# untitled.net
KiCad netlist of a schematic drawn in EAGLE
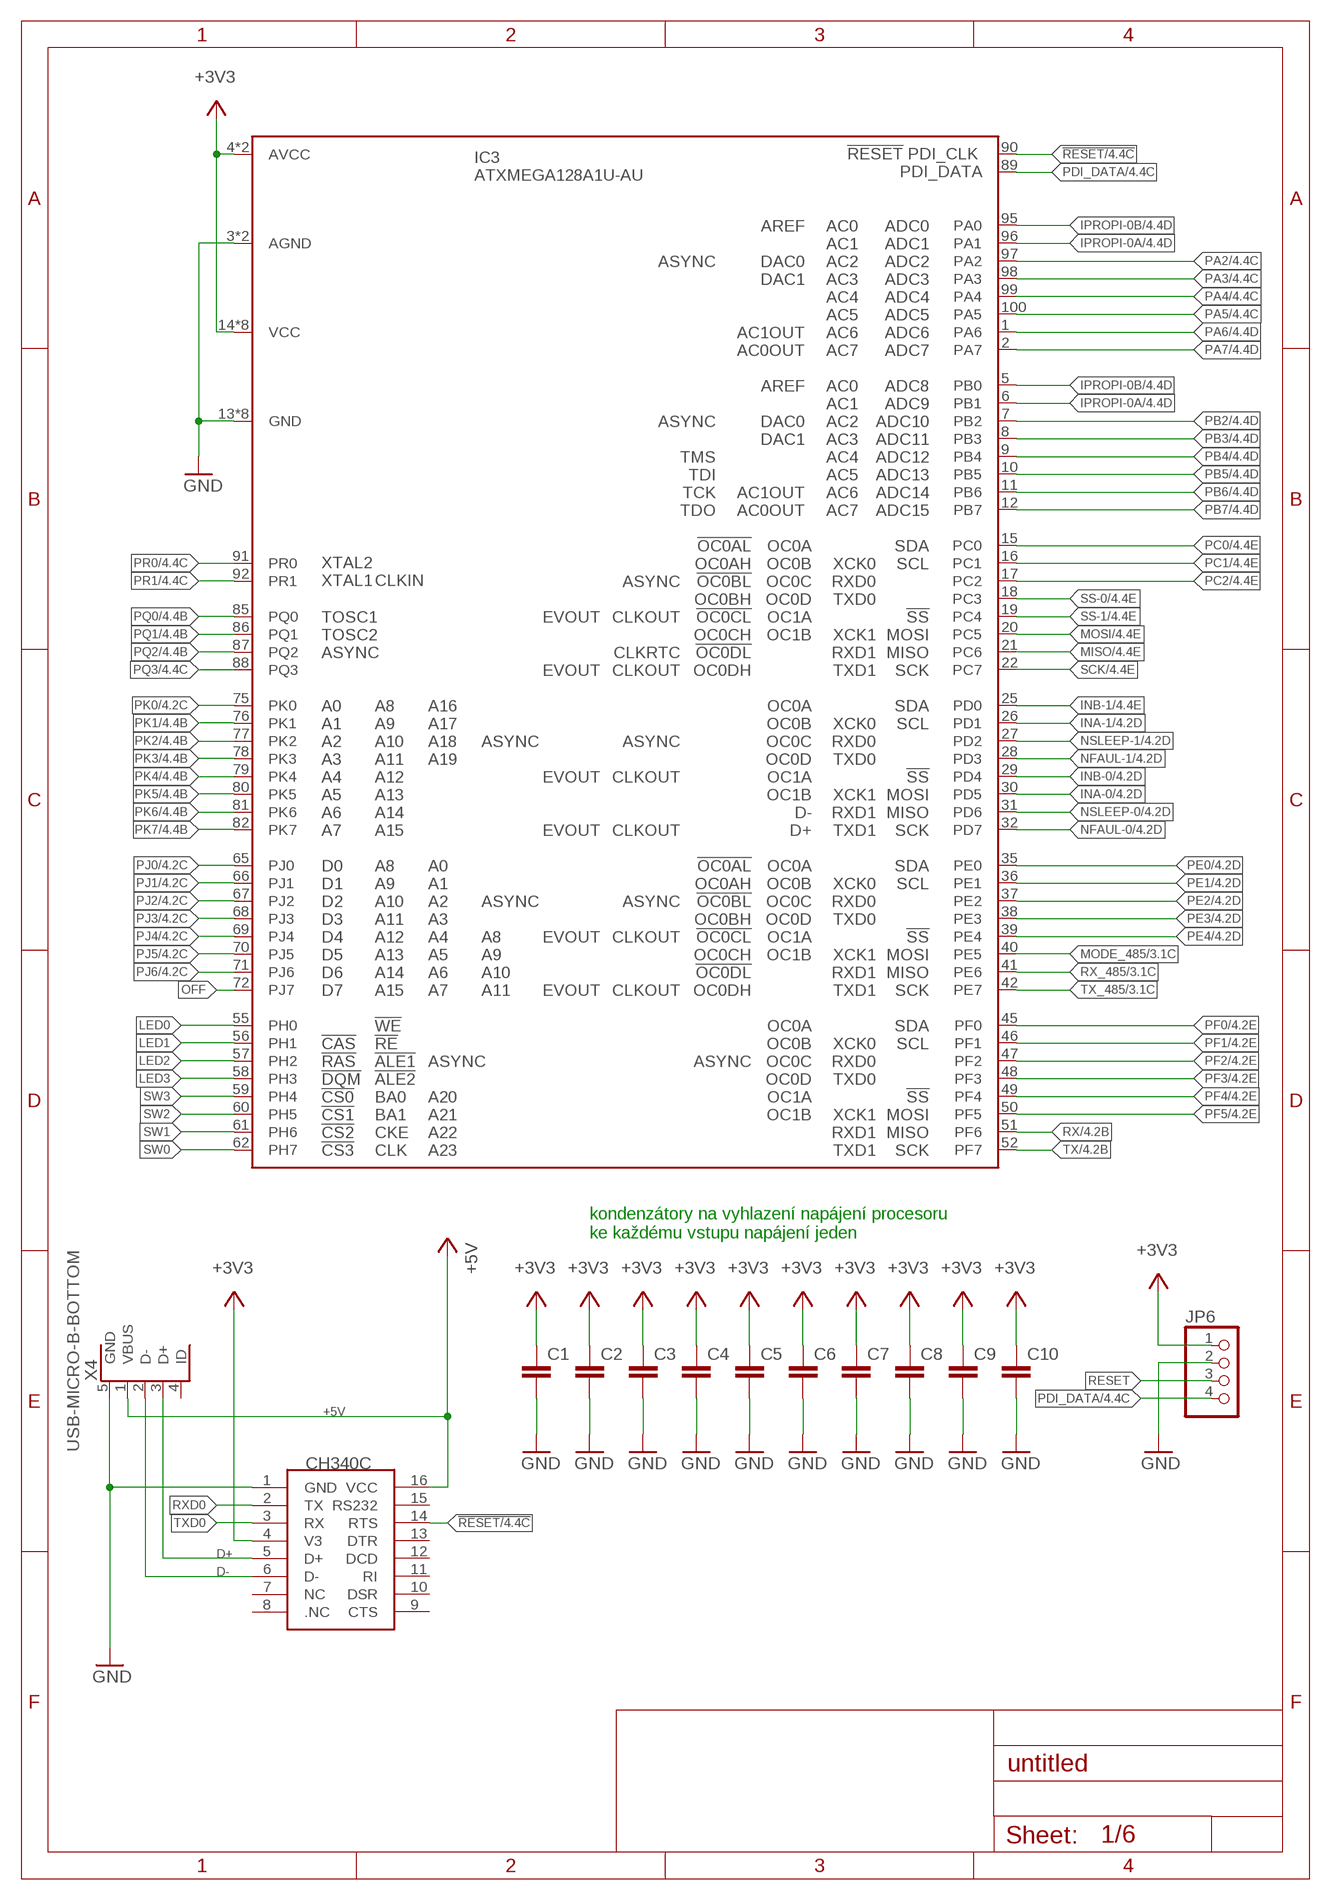
[diagram p0: schematic, sheet 1]
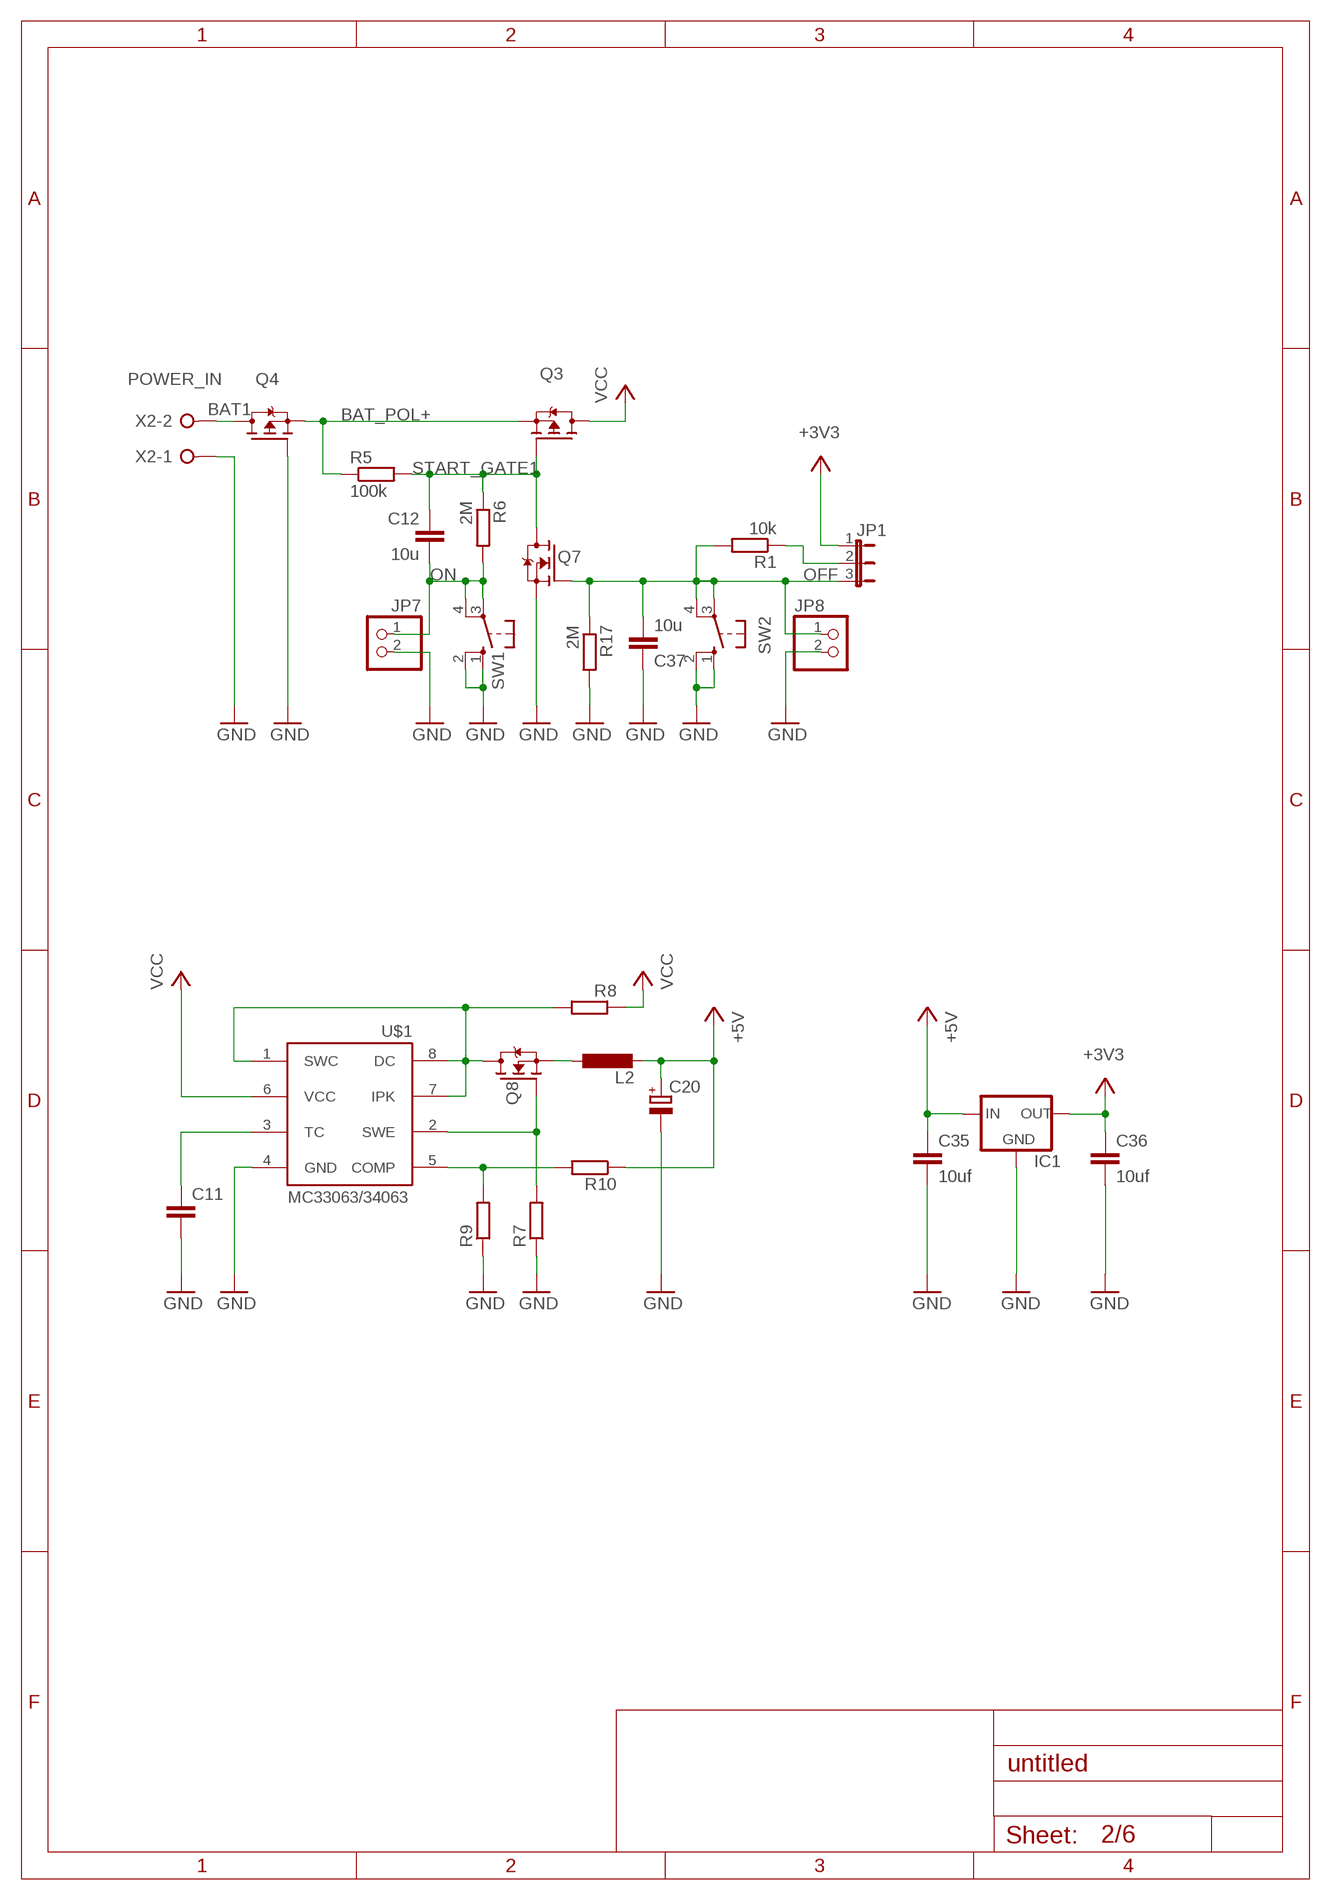
[diagram p1: schematic, sheet 2]
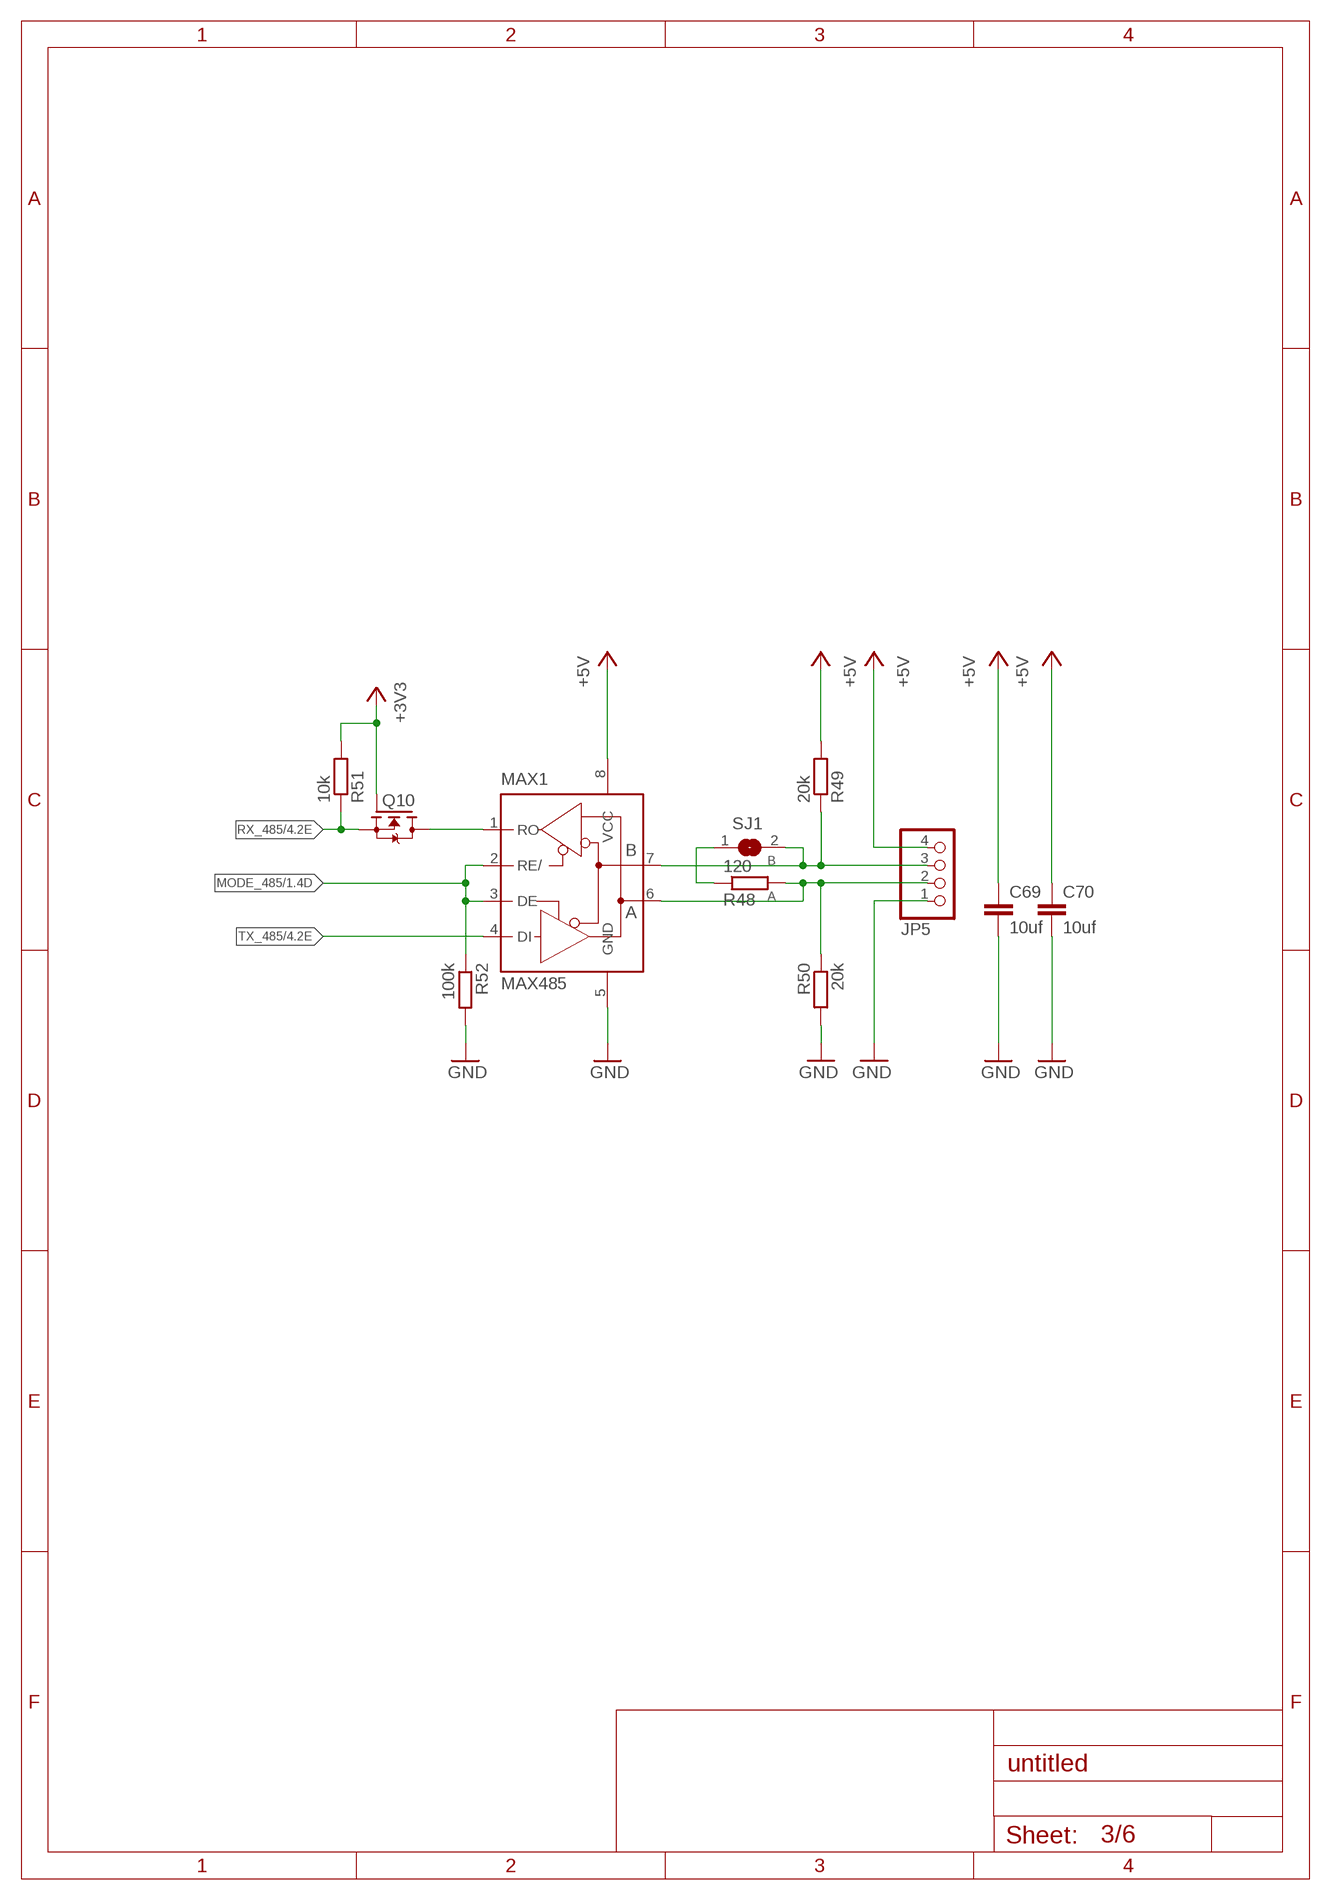
[diagram p2: schematic, sheet 3]
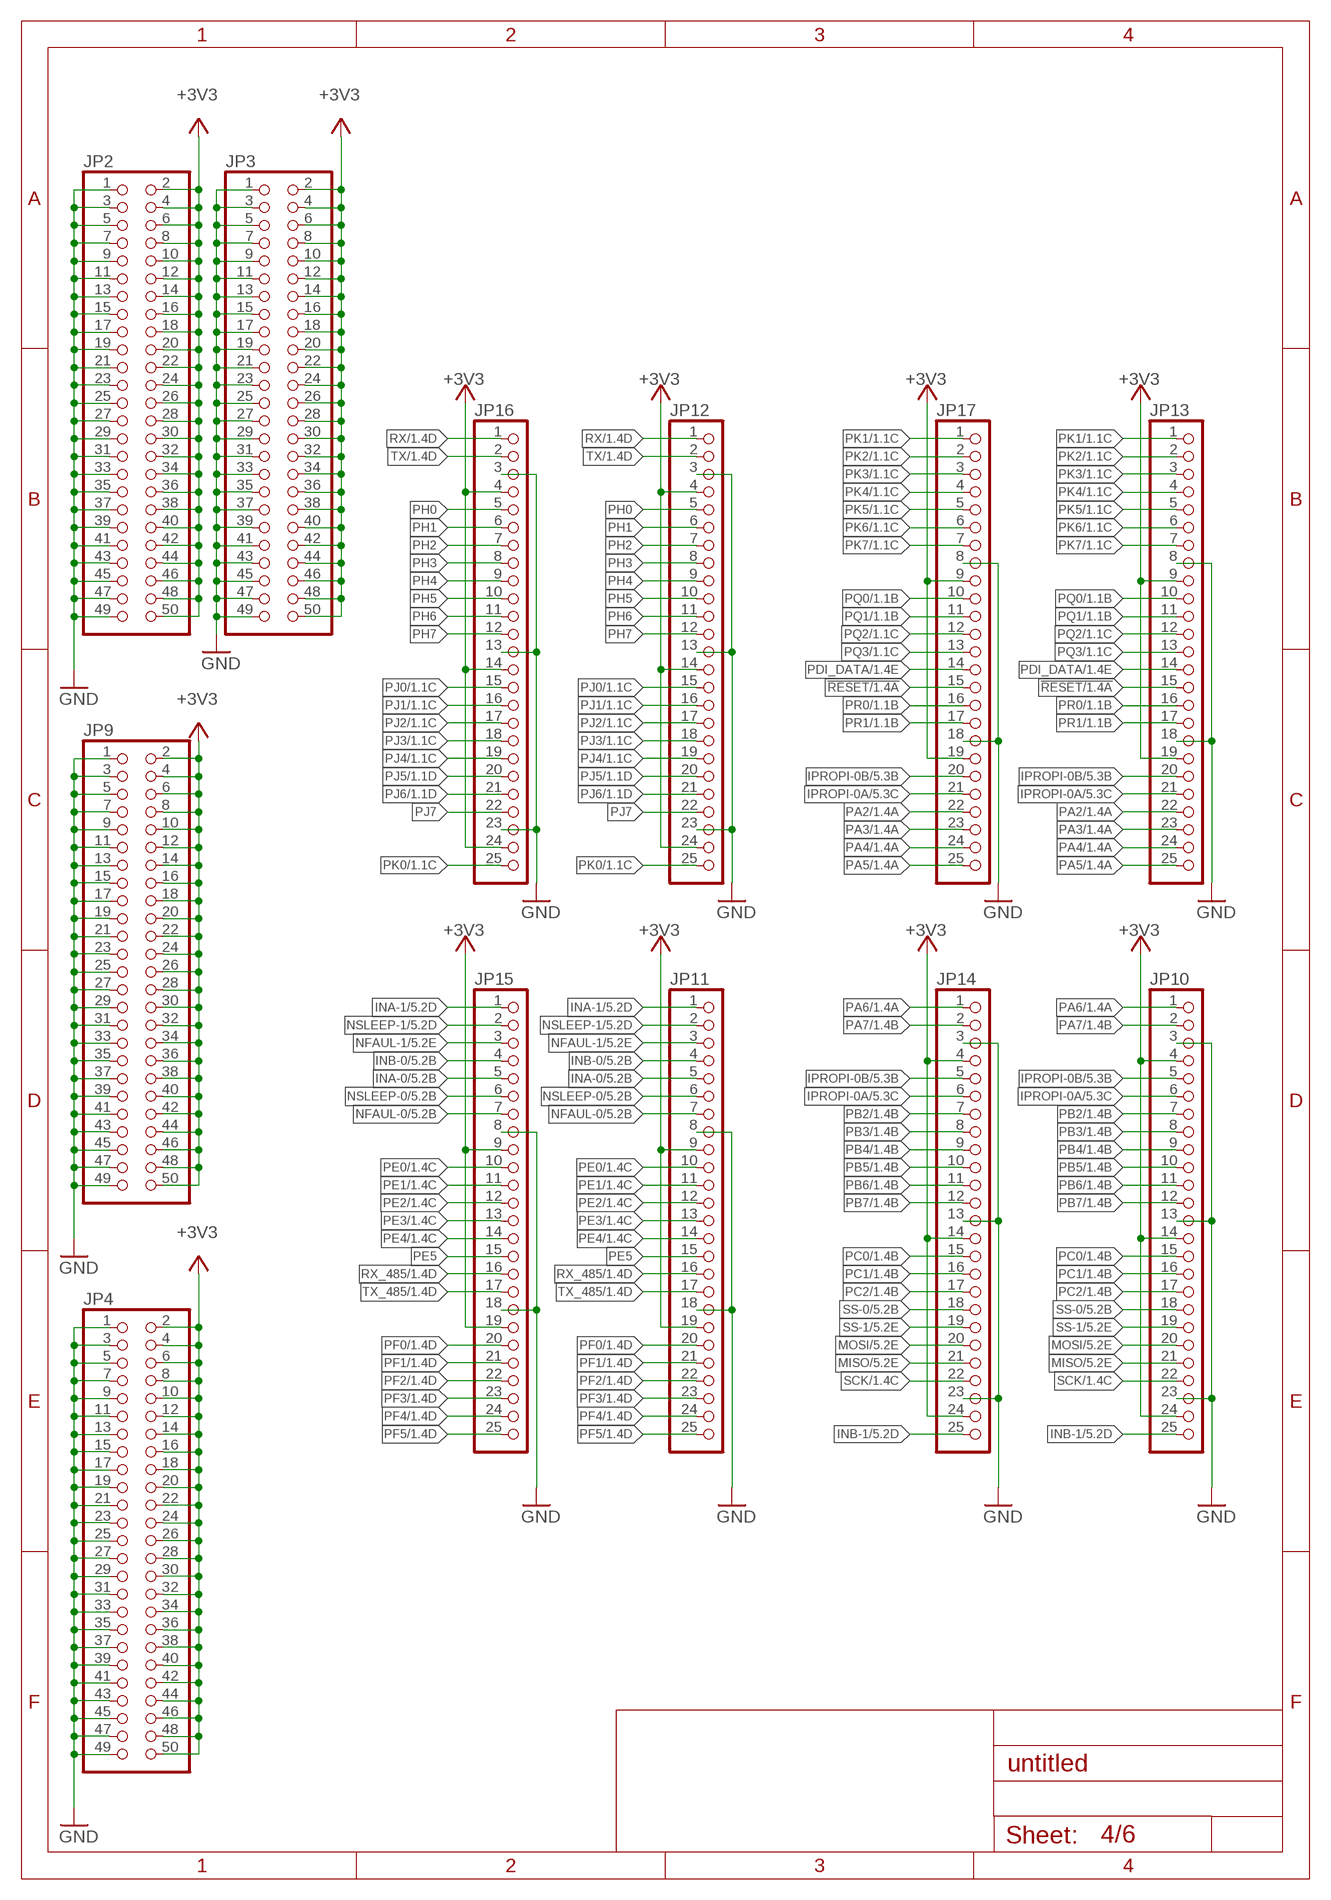
[diagram p3: schematic, sheet 4]
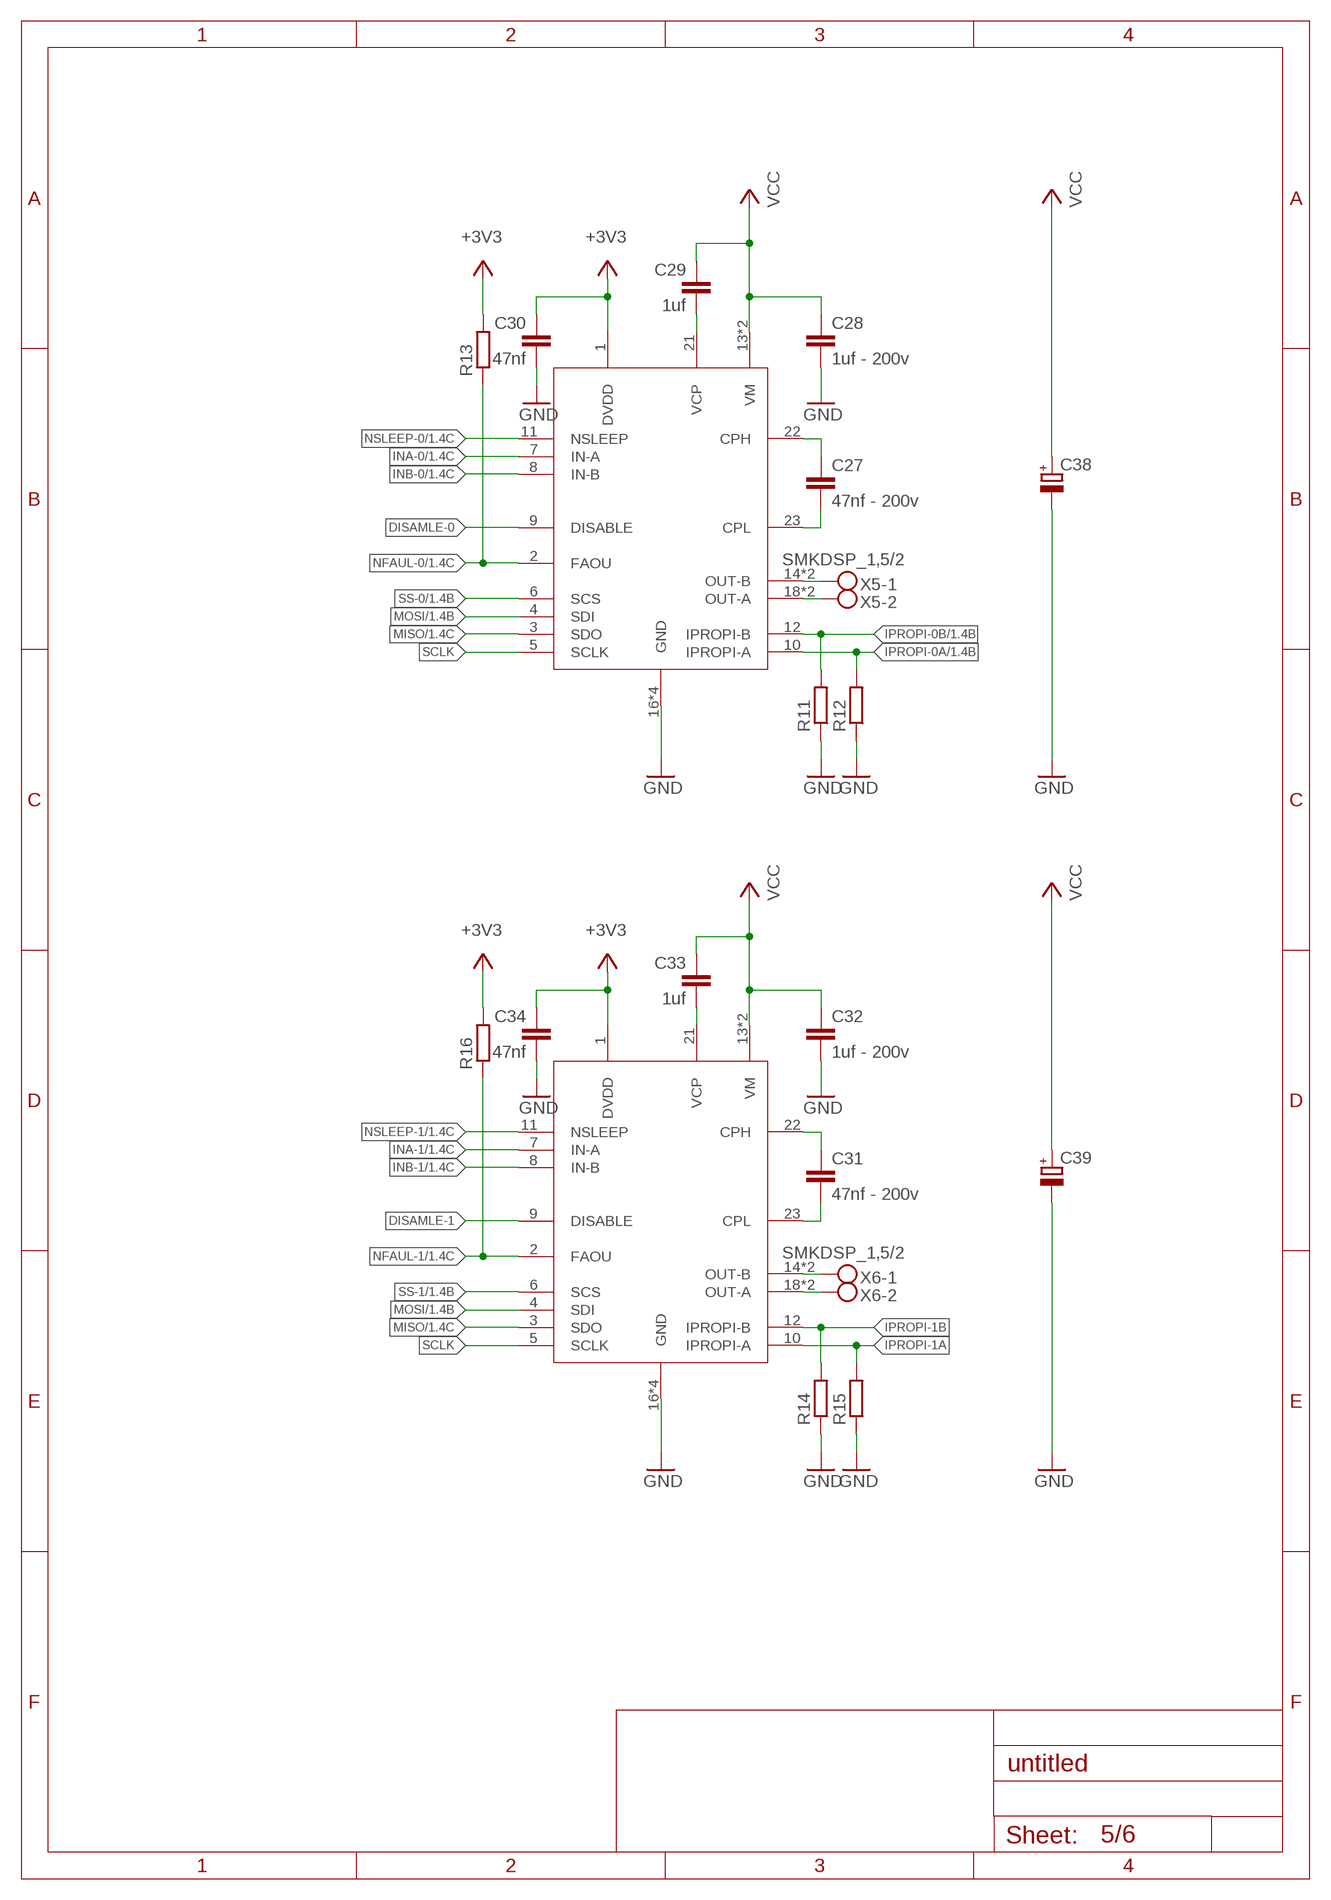
[diagram p4: schematic, sheet 5]
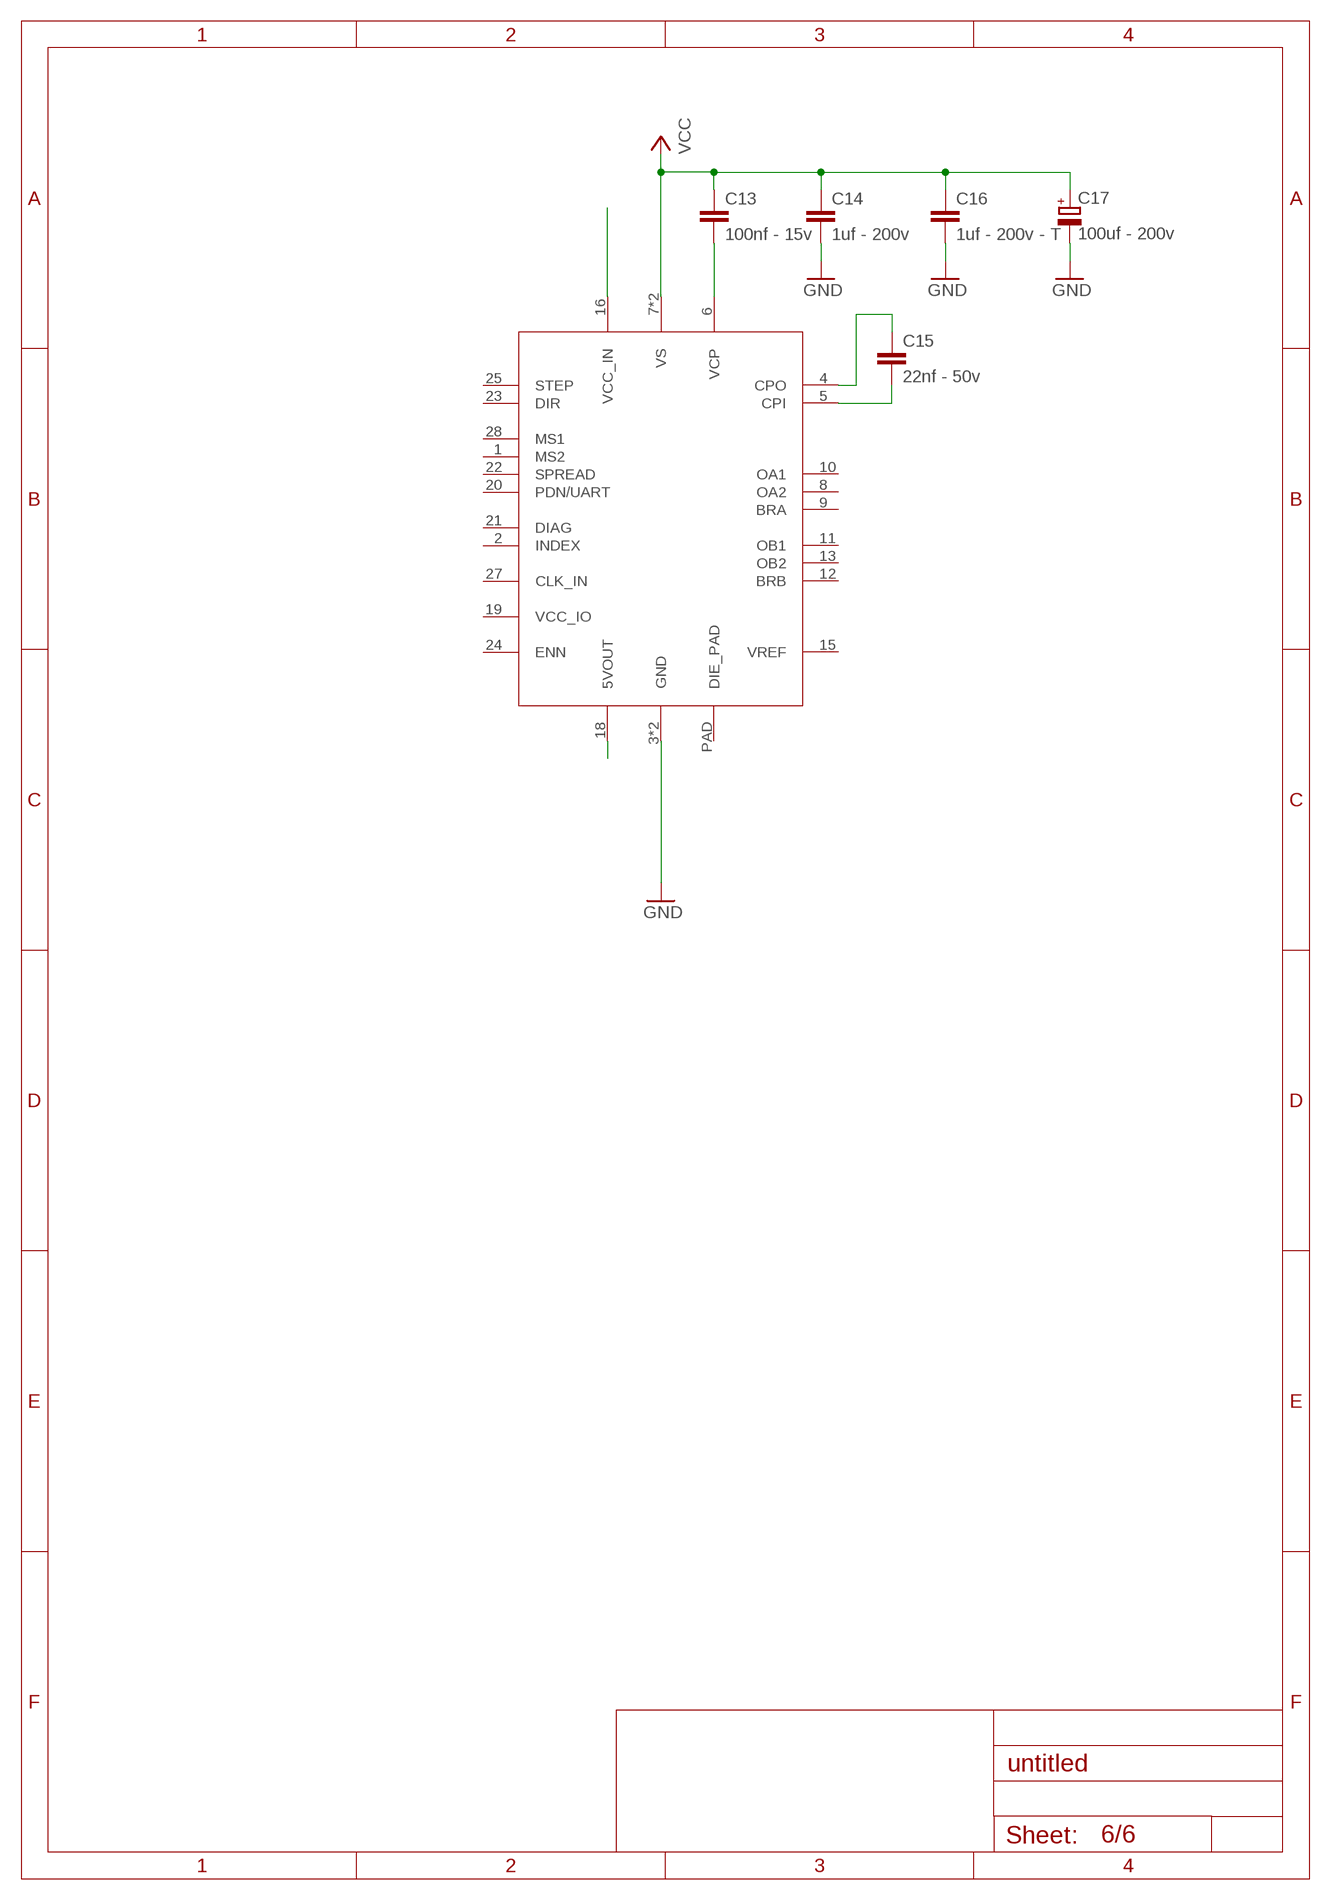
[diagram p5: schematic, sheet 6]

(export (version "E")
  (design (tool "Eeschema 10.0.6"))
  (components
    (comp (ref "C13")
      (value "100nf - 15v")
      (footprint "eagle-import:C1206")
      (libsource (lib "eagle-import") (part "rcl_334_C-EUC1206"))
    )
    (comp (ref "C14")
      (value "1uf - 200v")
      (footprint "eagle-import:C1206")
      (libsource (lib "eagle-import") (part "rcl_334_C-EUC1206"))
    )
    (comp (ref "C15")
      (value "22nf - 50v")
      (footprint "eagle-import:C1206")
      (libsource (lib "eagle-import") (part "rcl_334_C-EUC1206"))
    )
    (comp (ref "C16")
      (value "1uf - 200v - T")
      (footprint "eagle-import:C1206")
      (libsource (lib "eagle-import") (part "rcl_334_C-EUC1206"))
    )
    (comp (ref "C17")
      (value "100uf - 200v")
      (footprint "eagle-import:E5-10,5")
      (libsource (lib "eagle-import") (part "CPOL-EUE5-10.5"))
    )
    (comp (ref "U$3")
      (value "TMC2224")
      (footprint "eagle-import:QFN28")
      (libsource (lib "eagle-import") (part "TMC2224"))
    )
    (comp (ref "JP2")
      (value "PINHD-2X25")
      (footprint "eagle-import:2X25")
      (libsource (lib "eagle-import") (part "PINHD-2X25"))
    )
    (comp (ref "JP3")
      (value "PINHD-2X25")
      (footprint "eagle-import:2X25")
      (libsource (lib "eagle-import") (part "PINHD-2X25"))
    )
    (comp (ref "JP4")
      (value "PINHD-2X25")
      (footprint "eagle-import:2X25")
      (libsource (lib "eagle-import") (part "PINHD-2X25"))
    )
    (comp (ref "JP9")
      (value "PINHD-2X25")
      (footprint "eagle-import:2X25")
      (libsource (lib "eagle-import") (part "PINHD-2X25"))
    )
    (comp (ref "JP10")
      (value "PINHD-1X25")
      (footprint "eagle-import:1X25")
      (libsource (lib "eagle-import") (part "PINHD-1X25"))
    )
    (comp (ref "JP11")
      (value "PINHD-1X25")
      (footprint "eagle-import:1X25")
      (libsource (lib "eagle-import") (part "PINHD-1X25"))
    )
    (comp (ref "JP12")
      (value "PINHD-1X25")
      (footprint "eagle-import:1X25")
      (libsource (lib "eagle-import") (part "PINHD-1X25"))
    )
    (comp (ref "JP13")
      (value "PINHD-1X25")
      (footprint "eagle-import:1X25")
      (libsource (lib "eagle-import") (part "PINHD-1X25"))
    )
    (comp (ref "JP14")
      (value "PINHD-1X25")
      (footprint "eagle-import:1X25")
      (libsource (lib "eagle-import") (part "PINHD-1X25"))
    )
    (comp (ref "JP15")
      (value "PINHD-1X25")
      (footprint "eagle-import:1X25")
      (libsource (lib "eagle-import") (part "PINHD-1X25"))
    )
    (comp (ref "JP16")
      (value "PINHD-1X25")
      (footprint "eagle-import:1X25")
      (libsource (lib "eagle-import") (part "PINHD-1X25"))
    )
    (comp (ref "JP17")
      (value "PINHD-1X25")
      (footprint "eagle-import:1X25")
      (libsource (lib "eagle-import") (part "PINHD-1X25"))
    )
    (comp (ref "C11")
      (value "C-EUC0603")
      (footprint "eagle-import:C0603")
      (libsource (lib "eagle-import") (part "rcl_334_C-EUC0603"))
    )
    (comp (ref "C12")
      (value "10u")
      (footprint "eagle-import:C1206")
      (libsource (lib "eagle-import") (part "rcl_upravena_C-EUC1206"))
    )
    (comp (ref "C20")
      (value "CPOL-EUD")
      (footprint "eagle-import:PANASONIC_D")
      (libsource (lib "eagle-import") (part "rcl_334_CPOL-EUD"))
    )
    (comp (ref "C35")
      (value "10uf")
      (footprint "eagle-import:C0805")
      (libsource (lib "eagle-import") (part "C-EUC0805"))
    )
    (comp (ref "C36")
      (value "10uf")
      (footprint "eagle-import:C0805")
      (libsource (lib "eagle-import") (part "C-EUC0805"))
    )
    (comp (ref "C37")
      (value "10u")
      (footprint "eagle-import:C1206")
      (libsource (lib "eagle-import") (part "rcl_upravena_C-EUC1206"))
    )
    (comp (ref "IC1")
      (value "LM1117")
      (footprint "eagle-import:SOT223")
      (libsource (lib "eagle-import") (part "LM1117"))
    )
    (comp (ref "JP1")
      (value "JP2E")
      (footprint "eagle-import:JP2")
      (libsource (lib "eagle-import") (part "JP2E"))
    )
    (comp (ref "JP7")
      (value "PINHD-1X2")
      (footprint "eagle-import:1X02")
      (libsource (lib "eagle-import") (part "PINHD-1X2"))
    )
    (comp (ref "JP8")
      (value "PINHD-1X2")
      (footprint "eagle-import:1X02")
      (libsource (lib "eagle-import") (part "PINHD-1X2"))
    )
    (comp (ref "L2")
      (value "L-EUL3216C")
      (footprint "eagle-import:L3216C")
      (libsource (lib "eagle-import") (part "L-EUL3216C"))
    )
    (comp (ref "Q3")
      (value "P-MOSFET-MLP_HS")
      (footprint "eagle-import:MLP3.3X3.3_HS")
      (libsource (lib "eagle-import") (part "P-MOSFET-MLP_HS"))
    )
    (comp (ref "Q4")
      (value "P-MOSFET-MLP_HS")
      (footprint "eagle-import:MLP3.3X3.3_HS")
      (libsource (lib "eagle-import") (part "P-MOSFET-MLP_HS"))
    )
    (comp (ref "Q7")
      (value "N-MOSFET-SOT23-GSD")
      (footprint "eagle-import:SOT23")
      (libsource (lib "eagle-import") (part "N-MOSFET-SOT23-GSD"))
    )
    (comp (ref "Q8")
      (value "N-MOSFET-SOT23-GSD")
      (footprint "eagle-import:SOT23")
      (libsource (lib "eagle-import") (part "N-MOSFET-SOT23-GSD"))
    )
    (comp (ref "R1")
      (value "10k")
      (footprint "eagle-import:R0805")
      (libsource (lib "eagle-import") (part "rcl_upravena_R-EU_R0805"))
    )
    (comp (ref "R5")
      (value "100k")
      (footprint "eagle-import:R0805")
      (libsource (lib "eagle-import") (part "rcl_upravena_R-EU_R0805"))
    )
    (comp (ref "R6")
      (value "2M")
      (footprint "eagle-import:M0805")
      (libsource (lib "eagle-import") (part "rcl_upravena_R-EU_M0805"))
    )
    (comp (ref "R7")
      (value "R-EU_R0603")
      (footprint "eagle-import:R0603")
      (libsource (lib "eagle-import") (part "R-EU_R0603"))
    )
    (comp (ref "R8")
      (value "R-EU_R0603")
      (footprint "eagle-import:R0603")
      (libsource (lib "eagle-import") (part "R-EU_R0603"))
    )
    (comp (ref "R9")
      (value "R-EU_R0603")
      (footprint "eagle-import:R0603")
      (libsource (lib "eagle-import") (part "R-EU_R0603"))
    )
    (comp (ref "R10")
      (value "R-EU_R0603")
      (footprint "eagle-import:R0603")
      (libsource (lib "eagle-import") (part "R-EU_R0603"))
    )
    (comp (ref "R17")
      (value "2M")
      (footprint "eagle-import:M0805")
      (libsource (lib "eagle-import") (part "rcl_upravena_R-EU_M0805"))
    )
    (comp (ref "SW1")
      (value "10-XX")
      (footprint "eagle-import:B3F-10XX")
      (fields (field (name "MPN") "B3F-1000"))
      (libsource (lib "eagle-import") (part "10-XX"))
    )
    (comp (ref "SW2")
      (value "10-XX")
      (footprint "eagle-import:B3F-10XX")
      (fields (field (name "MPN") "B3F-1000"))
      (libsource (lib "eagle-import") (part "10-XX"))
    )
    (comp (ref "U$1")
      (value "MC33063/MC34063D")
      (footprint "eagle-import:SO08")
      (libsource (lib "eagle-import") (part "MC33063/MC34063D"))
    )
    (comp (ref "X2")
      (value "POWER_IN")
      (footprint "eagle-import:W237-132")
      (libsource (lib "eagle-import") (part "W237-02P"))
    )
    (comp (ref "C69")
      (value "10uf")
      (footprint "eagle-import:C0402K")
      (libsource (lib "eagle-import") (part "rcl_334_C-EUC0402K"))
    )
    (comp (ref "C70")
      (value "10uf")
      (footprint "eagle-import:C0402K")
      (libsource (lib "eagle-import") (part "rcl_334_C-EUC0402K"))
    )
    (comp (ref "JP5")
      (value "PINHD-1X4")
      (footprint "eagle-import:1X04")
      (libsource (lib "eagle-import") (part "PINHD-1X4"))
    )
    (comp (ref "MAX1")
      (value "MAX485")
      (footprint "eagle-import:SO08")
      (libsource (lib "eagle-import") (part "MAX485"))
    )
    (comp (ref "Q10")
      (value "N-MOSFET-SOT23-GSD")
      (footprint "eagle-import:SOT23")
      (libsource (lib "eagle-import") (part "N-MOSFET-SOT23-GSD"))
    )
    (comp (ref "R48")
      (value "120")
      (footprint "eagle-import:R0402")
      (libsource (lib "eagle-import") (part "R-EU_R0402"))
    )
    (comp (ref "R49")
      (value "20k")
      (footprint "eagle-import:R0402")
      (libsource (lib "eagle-import") (part "R-EU_R0402"))
    )
    (comp (ref "R50")
      (value "20k")
      (footprint "eagle-import:R0402")
      (libsource (lib "eagle-import") (part "R-EU_R0402"))
    )
    (comp (ref "R51")
      (value "10k")
      (footprint "eagle-import:R0402")
      (libsource (lib "eagle-import") (part "R-EU_R0402"))
    )
    (comp (ref "R52")
      (value "100k")
      (footprint "eagle-import:R0402")
      (libsource (lib "eagle-import") (part "R-EU_R0402"))
    )
    (comp (ref "SJ1") (value "SJ") (footprint "eagle-import:SJ") (libsource (lib "eagle-import") (part "SJ")))
    (comp (ref "C27")
      (value "47nf - 200v")
      (footprint "eagle-import:C0603")
      (libsource (lib "eagle-import") (part "rcl_334_C-EUC0603"))
    )
    (comp (ref "C28")
      (value "1uf - 200v")
      (footprint "eagle-import:C1206")
      (libsource (lib "eagle-import") (part "rcl_334_C-EUC1206"))
    )
    (comp (ref "C29")
      (value "1uf")
      (footprint "eagle-import:C1206")
      (libsource (lib "eagle-import") (part "rcl_334_C-EUC1206"))
    )
    (comp (ref "C30")
      (value "47nf")
      (footprint "eagle-import:C1206")
      (libsource (lib "eagle-import") (part "rcl_334_C-EUC1206"))
    )
    (comp (ref "C31")
      (value "47nf - 200v")
      (footprint "eagle-import:C0603")
      (libsource (lib "eagle-import") (part "rcl_334_C-EUC0603"))
    )
    (comp (ref "C32")
      (value "1uf - 200v")
      (footprint "eagle-import:C1206")
      (libsource (lib "eagle-import") (part "rcl_334_C-EUC1206"))
    )
    (comp (ref "C33")
      (value "1uf")
      (footprint "eagle-import:C1206")
      (libsource (lib "eagle-import") (part "rcl_334_C-EUC1206"))
    )
    (comp (ref "C34")
      (value "47nf")
      (footprint "eagle-import:C1206")
      (libsource (lib "eagle-import") (part "rcl_334_C-EUC1206"))
    )
    (comp (ref "C38")
      (value "CPOL-EUE5-10.5")
      (footprint "eagle-import:E5-10,5")
      (libsource (lib "eagle-import") (part "CPOL-EUE5-10.5"))
    )
    (comp (ref "C39")
      (value "CPOL-EUE5-10.5")
      (footprint "eagle-import:E5-10,5")
      (libsource (lib "eagle-import") (part "CPOL-EUE5-10.5"))
    )
    (comp (ref "R11")
      (value "R-EU_R0603")
      (footprint "eagle-import:R0603")
      (libsource (lib "eagle-import") (part "R-EU_R0603"))
    )
    (comp (ref "R12")
      (value "R-EU_R0603")
      (footprint "eagle-import:R0603")
      (libsource (lib "eagle-import") (part "R-EU_R0603"))
    )
    (comp (ref "R13")
      (value "R-EU_R0603")
      (footprint "eagle-import:R0603")
      (libsource (lib "eagle-import") (part "R-EU_R0603"))
    )
    (comp (ref "R14")
      (value "R-EU_R0603")
      (footprint "eagle-import:R0603")
      (libsource (lib "eagle-import") (part "R-EU_R0603"))
    )
    (comp (ref "R15")
      (value "R-EU_R0603")
      (footprint "eagle-import:R0603")
      (libsource (lib "eagle-import") (part "R-EU_R0603"))
    )
    (comp (ref "R16")
      (value "R-EU_R0603")
      (footprint "eagle-import:R0603")
      (libsource (lib "eagle-import") (part "R-EU_R0603"))
    )
    (comp (ref "U$2")
      (value "DER8873")
      (footprint "eagle-import:24HTSSOP")
      (libsource (lib "eagle-import") (part "DER8873"))
    )
    (comp (ref "U$6")
      (value "DER8873")
      (footprint "eagle-import:24HTSSOP")
      (libsource (lib "eagle-import") (part "DER8873"))
    )
    (comp (ref "X5")
      (value "SMKDSP_1,5/2")
      (footprint "eagle-import:SMKDSP_1,5_2")
      (fields (field (name "MF") "FARNELL") (field (name "MPN") "1733570"))
      (libsource (lib "eagle-import") (part "SMKDSP_1,5/2"))
    )
    (comp (ref "X6")
      (value "SMKDSP_1,5/2")
      (footprint "eagle-import:SMKDSP_1,5_2")
      (fields (field (name "MF") "FARNELL") (field (name "MPN") "1733570"))
      (libsource (lib "eagle-import") (part "SMKDSP_1,5/2"))
    )
    (comp (ref "C1")
      (value "C-EUC0402")
      (footprint "eagle-import:C0402")
      (libsource (lib "eagle-import") (part "C-EUC0402"))
    )
    (comp (ref "C2")
      (value "C-EUC0402")
      (footprint "eagle-import:C0402")
      (libsource (lib "eagle-import") (part "C-EUC0402"))
    )
    (comp (ref "C3")
      (value "C-EUC0402")
      (footprint "eagle-import:C0402")
      (libsource (lib "eagle-import") (part "C-EUC0402"))
    )
    (comp (ref "C4")
      (value "C-EUC0402")
      (footprint "eagle-import:C0402")
      (libsource (lib "eagle-import") (part "C-EUC0402"))
    )
    (comp (ref "C5")
      (value "C-EUC0402")
      (footprint "eagle-import:C0402")
      (libsource (lib "eagle-import") (part "C-EUC0402"))
    )
    (comp (ref "C6")
      (value "C-EUC0402")
      (footprint "eagle-import:C0402")
      (libsource (lib "eagle-import") (part "C-EUC0402"))
    )
    (comp (ref "C7")
      (value "C-EUC0402")
      (footprint "eagle-import:C0402")
      (libsource (lib "eagle-import") (part "C-EUC0402"))
    )
    (comp (ref "C8")
      (value "C-EUC0402")
      (footprint "eagle-import:C0402")
      (libsource (lib "eagle-import") (part "C-EUC0402"))
    )
    (comp (ref "C9")
      (value "C-EUC0402")
      (footprint "eagle-import:C0402")
      (libsource (lib "eagle-import") (part "C-EUC0402"))
    )
    (comp (ref "C10")
      (value "C-EUC0402")
      (footprint "eagle-import:C0402")
      (libsource (lib "eagle-import") (part "C-EUC0402"))
    )
    (comp (ref "CH2")
      (value "CH340C")
      (footprint "eagle-import:SOIC16")
      (libsource (lib "eagle-import") (part "CH340C"))
    )
    (comp (ref "IC3")
      (value "ATXMEGA128A1U-AU")
      (footprint "eagle-import:TQFP100")
      (libsource (lib "eagle-import") (part "ATXMEGAA1U-AU128"))
    )
    (comp (ref "JP6")
      (value "PINHD-1X4")
      (footprint "eagle-import:1X04")
      (libsource (lib "eagle-import") (part "PINHD-1X4"))
    )
    (comp (ref "X4")
      (value "USB-MICRO-B-BOTTOM")
      (footprint "eagle-import:USB-MICRO-B-BOTTOM-MOLEX")
      (libsource (lib "eagle-import") (part "USB-MICRO-B-BOTTOM"))
    )
  )
  (nets
    (net (code "1") (name "+3V3") (class "Default")
      (node (ref "C1") (pin "1") (pinfunction "1_1") (pintype "passive"))
      (node (ref "C10") (pin "1") (pinfunction "1_1") (pintype "passive"))
      (node (ref "C2") (pin "1") (pinfunction "1_1") (pintype "passive"))
      (node (ref "C3") (pin "1") (pinfunction "1_1") (pintype "passive"))
      (node (ref "C30") (pin "1") (pinfunction "1_1") (pintype "passive"))
      (node (ref "C34") (pin "1") (pinfunction "1_1") (pintype "passive"))
      (node (ref "C36") (pin "1") (pinfunction "1_1") (pintype "passive"))
      (node (ref "C4") (pin "1") (pinfunction "1_1") (pintype "passive"))
      (node (ref "C5") (pin "1") (pinfunction "1_1") (pintype "passive"))
      (node (ref "C6") (pin "1") (pinfunction "1_1") (pintype "passive"))
      (node (ref "C7") (pin "1") (pinfunction "1_1") (pintype "passive"))
      (node (ref "C8") (pin "1") (pinfunction "1_1") (pintype "passive"))
      (node (ref "C9") (pin "1") (pinfunction "1_1") (pintype "passive"))
      (node (ref "CH2") (pin "4") (pinfunction "V3_4") (pintype "bidirectional"))
      (node (ref "IC1") (pin "2") (pinfunction "OUT_2") (pintype "passive"))
      (node (ref "IC3") (pin "14") (pinfunction "VCC_14") (pintype "power_in"))
      (node (ref "IC3") (pin "24") (pinfunction "VCC_24") (pintype "power_in"))
      (node (ref "IC3") (pin "34") (pinfunction "VCC_34") (pintype "power_in"))
      (node (ref "IC3") (pin "4") (pinfunction "AVCC_4") (pintype "power_in"))
      (node (ref "IC3") (pin "44") (pinfunction "VCC_44") (pintype "power_in"))
      (node (ref "IC3") (pin "54") (pinfunction "VCC_54") (pintype "power_in"))
      (node (ref "IC3") (pin "64") (pinfunction "VCC_64") (pintype "power_in"))
      (node (ref "IC3") (pin "74") (pinfunction "VCC_74") (pintype "power_in"))
      (node (ref "IC3") (pin "83") (pinfunction "VCC_83") (pintype "power_in"))
      (node (ref "IC3") (pin "94") (pinfunction "AVCC_94") (pintype "power_in"))
      (node (ref "JP1") (pin "1") (pinfunction "1_1") (pintype "passive"))
      (node (ref "JP10") (pin "14") (pinfunction "14_14") (pintype "passive"))
      (node (ref "JP10") (pin "24") (pinfunction "24_24") (pintype "passive"))
      (node (ref "JP10") (pin "4") (pinfunction "4_4") (pintype "passive"))
      (node (ref "JP11") (pin "19") (pinfunction "19_19") (pintype "passive"))
      (node (ref "JP11") (pin "9") (pinfunction "9_9") (pintype "passive"))
      (node (ref "JP12") (pin "14") (pinfunction "14_14") (pintype "passive"))
      (node (ref "JP12") (pin "24") (pinfunction "24_24") (pintype "passive"))
      (node (ref "JP12") (pin "4") (pinfunction "4_4") (pintype "passive"))
      (node (ref "JP13") (pin "19") (pinfunction "19_19") (pintype "passive"))
      (node (ref "JP13") (pin "9") (pinfunction "9_9") (pintype "passive"))
      (node (ref "JP14") (pin "14") (pinfunction "14_14") (pintype "passive"))
      (node (ref "JP14") (pin "24") (pinfunction "24_24") (pintype "passive"))
      (node (ref "JP14") (pin "4") (pinfunction "4_4") (pintype "passive"))
      (node (ref "JP15") (pin "19") (pinfunction "19_19") (pintype "passive"))
      (node (ref "JP15") (pin "9") (pinfunction "9_9") (pintype "passive"))
      (node (ref "JP16") (pin "14") (pinfunction "14_14") (pintype "passive"))
      (node (ref "JP16") (pin "24") (pinfunction "24_24") (pintype "passive"))
      (node (ref "JP16") (pin "4") (pinfunction "4_4") (pintype "passive"))
      (node (ref "JP17") (pin "19") (pinfunction "19_19") (pintype "passive"))
      (node (ref "JP17") (pin "9") (pinfunction "9_9") (pintype "passive"))
      (node (ref "JP2") (pin "10") (pinfunction "10_10") (pintype "passive"))
      (node (ref "JP2") (pin "12") (pinfunction "12_12") (pintype "passive"))
      (node (ref "JP2") (pin "14") (pinfunction "14_14") (pintype "passive"))
      (node (ref "JP2") (pin "16") (pinfunction "16_16") (pintype "passive"))
      (node (ref "JP2") (pin "18") (pinfunction "18_18") (pintype "passive"))
      (node (ref "JP2") (pin "2") (pinfunction "2_2") (pintype "passive"))
      (node (ref "JP2") (pin "20") (pinfunction "20_20") (pintype "passive"))
      (node (ref "JP2") (pin "22") (pinfunction "22_22") (pintype "passive"))
      (node (ref "JP2") (pin "24") (pinfunction "24_24") (pintype "passive"))
      (node (ref "JP2") (pin "26") (pinfunction "26_26") (pintype "passive"))
      (node (ref "JP2") (pin "28") (pinfunction "28_28") (pintype "passive"))
      (node (ref "JP2") (pin "30") (pinfunction "30_30") (pintype "passive"))
      (node (ref "JP2") (pin "32") (pinfunction "32_32") (pintype "passive"))
      (node (ref "JP2") (pin "34") (pinfunction "34_34") (pintype "passive"))
      (node (ref "JP2") (pin "36") (pinfunction "36_36") (pintype "passive"))
      (node (ref "JP2") (pin "38") (pinfunction "38_38") (pintype "passive"))
      (node (ref "JP2") (pin "4") (pinfunction "4_4") (pintype "passive"))
      (node (ref "JP2") (pin "40") (pinfunction "40_40") (pintype "passive"))
      (node (ref "JP2") (pin "42") (pinfunction "42_42") (pintype "passive"))
      (node (ref "JP2") (pin "44") (pinfunction "44_44") (pintype "passive"))
      (node (ref "JP2") (pin "46") (pinfunction "46_46") (pintype "passive"))
      (node (ref "JP2") (pin "48") (pinfunction "48_48") (pintype "passive"))
      (node (ref "JP2") (pin "50") (pinfunction "50_50") (pintype "passive"))
      (node (ref "JP2") (pin "6") (pinfunction "6_6") (pintype "passive"))
      (node (ref "JP2") (pin "8") (pinfunction "8_8") (pintype "passive"))
      (node (ref "JP3") (pin "10") (pinfunction "10_10") (pintype "passive"))
      (node (ref "JP3") (pin "12") (pinfunction "12_12") (pintype "passive"))
      (node (ref "JP3") (pin "14") (pinfunction "14_14") (pintype "passive"))
      (node (ref "JP3") (pin "16") (pinfunction "16_16") (pintype "passive"))
      (node (ref "JP3") (pin "18") (pinfunction "18_18") (pintype "passive"))
      (node (ref "JP3") (pin "2") (pinfunction "2_2") (pintype "passive"))
      (node (ref "JP3") (pin "20") (pinfunction "20_20") (pintype "passive"))
      (node (ref "JP3") (pin "22") (pinfunction "22_22") (pintype "passive"))
      (node (ref "JP3") (pin "24") (pinfunction "24_24") (pintype "passive"))
      (node (ref "JP3") (pin "26") (pinfunction "26_26") (pintype "passive"))
      (node (ref "JP3") (pin "28") (pinfunction "28_28") (pintype "passive"))
      (node (ref "JP3") (pin "30") (pinfunction "30_30") (pintype "passive"))
      (node (ref "JP3") (pin "32") (pinfunction "32_32") (pintype "passive"))
      (node (ref "JP3") (pin "34") (pinfunction "34_34") (pintype "passive"))
      (node (ref "JP3") (pin "36") (pinfunction "36_36") (pintype "passive"))
      (node (ref "JP3") (pin "38") (pinfunction "38_38") (pintype "passive"))
      (node (ref "JP3") (pin "4") (pinfunction "4_4") (pintype "passive"))
      (node (ref "JP3") (pin "40") (pinfunction "40_40") (pintype "passive"))
      (node (ref "JP3") (pin "42") (pinfunction "42_42") (pintype "passive"))
      (node (ref "JP3") (pin "44") (pinfunction "44_44") (pintype "passive"))
      (node (ref "JP3") (pin "46") (pinfunction "46_46") (pintype "passive"))
      (node (ref "JP3") (pin "48") (pinfunction "48_48") (pintype "passive"))
      (node (ref "JP3") (pin "50") (pinfunction "50_50") (pintype "passive"))
      (node (ref "JP3") (pin "6") (pinfunction "6_6") (pintype "passive"))
      (node (ref "JP3") (pin "8") (pinfunction "8_8") (pintype "passive"))
      (node (ref "JP4") (pin "10") (pinfunction "10_10") (pintype "passive"))
      (node (ref "JP4") (pin "12") (pinfunction "12_12") (pintype "passive"))
      (node (ref "JP4") (pin "14") (pinfunction "14_14") (pintype "passive"))
      (node (ref "JP4") (pin "16") (pinfunction "16_16") (pintype "passive"))
      (node (ref "JP4") (pin "18") (pinfunction "18_18") (pintype "passive"))
      (node (ref "JP4") (pin "2") (pinfunction "2_2") (pintype "passive"))
      (node (ref "JP4") (pin "20") (pinfunction "20_20") (pintype "passive"))
      (node (ref "JP4") (pin "22") (pinfunction "22_22") (pintype "passive"))
      (node (ref "JP4") (pin "24") (pinfunction "24_24") (pintype "passive"))
      (node (ref "JP4") (pin "26") (pinfunction "26_26") (pintype "passive"))
      (node (ref "JP4") (pin "28") (pinfunction "28_28") (pintype "passive"))
      (node (ref "JP4") (pin "30") (pinfunction "30_30") (pintype "passive"))
      (node (ref "JP4") (pin "32") (pinfunction "32_32") (pintype "passive"))
      (node (ref "JP4") (pin "34") (pinfunction "34_34") (pintype "passive"))
      (node (ref "JP4") (pin "36") (pinfunction "36_36") (pintype "passive"))
      (node (ref "JP4") (pin "38") (pinfunction "38_38") (pintype "passive"))
      (node (ref "JP4") (pin "4") (pinfunction "4_4") (pintype "passive"))
      (node (ref "JP4") (pin "40") (pinfunction "40_40") (pintype "passive"))
      (node (ref "JP4") (pin "42") (pinfunction "42_42") (pintype "passive"))
      (node (ref "JP4") (pin "44") (pinfunction "44_44") (pintype "passive"))
      (node (ref "JP4") (pin "46") (pinfunction "46_46") (pintype "passive"))
      (node (ref "JP4") (pin "48") (pinfunction "48_48") (pintype "passive"))
      (node (ref "JP4") (pin "50") (pinfunction "50_50") (pintype "passive"))
      (node (ref "JP4") (pin "6") (pinfunction "6_6") (pintype "passive"))
      (node (ref "JP4") (pin "8") (pinfunction "8_8") (pintype "passive"))
      (node (ref "JP6") (pin "1") (pinfunction "1_1") (pintype "passive"))
      (node (ref "JP9") (pin "10") (pinfunction "10_10") (pintype "passive"))
      (node (ref "JP9") (pin "12") (pinfunction "12_12") (pintype "passive"))
      (node (ref "JP9") (pin "14") (pinfunction "14_14") (pintype "passive"))
      (node (ref "JP9") (pin "16") (pinfunction "16_16") (pintype "passive"))
      (node (ref "JP9") (pin "18") (pinfunction "18_18") (pintype "passive"))
      (node (ref "JP9") (pin "2") (pinfunction "2_2") (pintype "passive"))
      (node (ref "JP9") (pin "20") (pinfunction "20_20") (pintype "passive"))
      (node (ref "JP9") (pin "22") (pinfunction "22_22") (pintype "passive"))
      (node (ref "JP9") (pin "24") (pinfunction "24_24") (pintype "passive"))
      (node (ref "JP9") (pin "26") (pinfunction "26_26") (pintype "passive"))
      (node (ref "JP9") (pin "28") (pinfunction "28_28") (pintype "passive"))
      (node (ref "JP9") (pin "30") (pinfunction "30_30") (pintype "passive"))
      (node (ref "JP9") (pin "32") (pinfunction "32_32") (pintype "passive"))
      (node (ref "JP9") (pin "34") (pinfunction "34_34") (pintype "passive"))
      (node (ref "JP9") (pin "36") (pinfunction "36_36") (pintype "passive"))
      (node (ref "JP9") (pin "38") (pinfunction "38_38") (pintype "passive"))
      (node (ref "JP9") (pin "4") (pinfunction "4_4") (pintype "passive"))
      (node (ref "JP9") (pin "40") (pinfunction "40_40") (pintype "passive"))
      (node (ref "JP9") (pin "42") (pinfunction "42_42") (pintype "passive"))
      (node (ref "JP9") (pin "44") (pinfunction "44_44") (pintype "passive"))
      (node (ref "JP9") (pin "46") (pinfunction "46_46") (pintype "passive"))
      (node (ref "JP9") (pin "48") (pinfunction "48_48") (pintype "passive"))
      (node (ref "JP9") (pin "50") (pinfunction "50_50") (pintype "passive"))
      (node (ref "JP9") (pin "6") (pinfunction "6_6") (pintype "passive"))
      (node (ref "JP9") (pin "8") (pinfunction "8_8") (pintype "passive"))
      (node (ref "Q10") (pin "1") (pinfunction "G_1") (pintype "passive"))
      (node (ref "R13") (pin "2") (pinfunction "2_2") (pintype "passive"))
      (node (ref "R16") (pin "2") (pinfunction "2_2") (pintype "passive"))
      (node (ref "R51") (pin "2") (pinfunction "2_2") (pintype "passive"))
      (node (ref "U$2") (pin "1") (pinfunction "DVDD_1") (pintype "bidirectional"))
      (node (ref "U$6") (pin "1") (pinfunction "DVDD_1") (pintype "bidirectional"))
    )
    (net (code "2") (name "+5V") (class "Default")
      (node (ref "C20") (pin "+") (pinfunction "+_+") (pintype "passive"))
      (node (ref "C35") (pin "1") (pinfunction "1_1") (pintype "passive"))
      (node (ref "C69") (pin "1") (pinfunction "1_1") (pintype "passive"))
      (node (ref "C70") (pin "1") (pinfunction "1_1") (pintype "passive"))
      (node (ref "CH2") (pin "16") (pinfunction "VCC_16") (pintype "bidirectional"))
      (node (ref "IC1") (pin "3") (pinfunction "IN_3") (pintype "input"))
      (node (ref "JP5") (pin "4") (pinfunction "4_4") (pintype "passive"))
      (node (ref "L2") (pin "2") (pinfunction "2_2") (pintype "passive"))
      (node (ref "MAX1") (pin "8") (pinfunction "VCC_8") (pintype "bidirectional"))
      (node (ref "R10") (pin "1") (pinfunction "1_1") (pintype "passive"))
      (node (ref "R49") (pin "2") (pinfunction "2_2") (pintype "passive"))
      (node (ref "X4") (pin "1") (pinfunction "VBUS_1") (pintype "passive"))
    )
    (net (code "3") (name "A") (class "Default")
      (node (ref "JP5") (pin "2") (pinfunction "2_2") (pintype "passive"))
      (node (ref "MAX1") (pin "6") (pinfunction "A_6") (pintype "passive"))
      (node (ref "R48") (pin "2") (pinfunction "2_2") (pintype "passive"))
      (node (ref "R50") (pin "1") (pinfunction "1_1") (pintype "passive"))
    )
    (net (code "4") (name "B") (class "Default")
      (node (ref "JP5") (pin "3") (pinfunction "3_3") (pintype "passive"))
      (node (ref "MAX1") (pin "7") (pinfunction "B_7") (pintype "passive"))
      (node (ref "R49") (pin "1") (pinfunction "1_1") (pintype "passive"))
      (node (ref "SJ1") (pin "2") (pinfunction "2_2") (pintype "passive"))
    )
    (net (code "5") (name "BAT1") (class "Default")
      (node (ref "Q4") (pin "5") (pinfunction "D_5") (pintype "passive"))
      (node (ref "Q4") (pin "6") (pinfunction "D_6") (pintype "passive"))
      (node (ref "Q4") (pin "7") (pinfunction "D_7") (pintype "passive"))
      (node (ref "Q4") (pin "8") (pinfunction "D_8") (pintype "passive"))
      (node (ref "X2") (pin "2") (pinfunction "KL_2") (pintype "passive"))
    )
    (net (code "6") (name "BAT_POL+") (class "Default")
      (node (ref "Q3") (pin "1") (pinfunction "S_1") (pintype "passive"))
      (node (ref "Q3") (pin "2") (pinfunction "S_2") (pintype "passive"))
      (node (ref "Q3") (pin "3") (pinfunction "S_3") (pintype "passive"))
      (node (ref "Q4") (pin "1") (pinfunction "S_1") (pintype "passive"))
      (node (ref "Q4") (pin "2") (pinfunction "S_2") (pintype "passive"))
      (node (ref "Q4") (pin "3") (pinfunction "S_3") (pintype "passive"))
      (node (ref "R5") (pin "1") (pinfunction "1_1") (pintype "passive"))
    )
    (net (code "7") (name "D+") (class "Default")
      (node (ref "CH2") (pin "5") (pinfunction "D+_5") (pintype "bidirectional"))
      (node (ref "X4") (pin "3") (pinfunction "D+_3") (pintype "bidirectional"))
    )
    (net (code "8") (name "D-") (class "Default")
      (node (ref "CH2") (pin "6") (pinfunction "D-_6") (pintype "bidirectional"))
      (node (ref "X4") (pin "2") (pinfunction "D-_2") (pintype "bidirectional"))
    )
    (net (code "9") (name "DISAMLE-0") (class "Default")
      (node (ref "U$2") (pin "9") (pinfunction "DISABLE_9") (pintype "bidirectional"))
    )
    (net (code "10") (name "DISAMLE-1") (class "Default")
      (node (ref "U$6") (pin "9") (pinfunction "DISABLE_9") (pintype "bidirectional"))
    )
    (net (code "11") (name "GND") (class "Default")
      (node (ref "C1") (pin "2") (pinfunction "2_2") (pintype "passive"))
      (node (ref "C10") (pin "2") (pinfunction "2_2") (pintype "passive"))
      (node (ref "C11") (pin "2") (pinfunction "2_2") (pintype "passive"))
      (node (ref "C14") (pin "2") (pinfunction "2_2") (pintype "passive"))
      (node (ref "C16") (pin "2") (pinfunction "2_2") (pintype "passive"))
      (node (ref "C17") (pin "-") (pinfunction "-_-") (pintype "passive"))
      (node (ref "C2") (pin "2") (pinfunction "2_2") (pintype "passive"))
      (node (ref "C20") (pin "-") (pinfunction "-_-") (pintype "passive"))
      (node (ref "C28") (pin "2") (pinfunction "2_2") (pintype "passive"))
      (node (ref "C3") (pin "2") (pinfunction "2_2") (pintype "passive"))
      (node (ref "C30") (pin "2") (pinfunction "2_2") (pintype "passive"))
      (node (ref "C32") (pin "2") (pinfunction "2_2") (pintype "passive"))
      (node (ref "C34") (pin "2") (pinfunction "2_2") (pintype "passive"))
      (node (ref "C35") (pin "2") (pinfunction "2_2") (pintype "passive"))
      (node (ref "C36") (pin "2") (pinfunction "2_2") (pintype "passive"))
      (node (ref "C37") (pin "1") (pinfunction "1_1") (pintype "passive"))
      (node (ref "C38") (pin "-") (pinfunction "-_-") (pintype "passive"))
      (node (ref "C39") (pin "-") (pinfunction "-_-") (pintype "passive"))
      (node (ref "C4") (pin "2") (pinfunction "2_2") (pintype "passive"))
      (node (ref "C5") (pin "2") (pinfunction "2_2") (pintype "passive"))
      (node (ref "C6") (pin "2") (pinfunction "2_2") (pintype "passive"))
      (node (ref "C69") (pin "2") (pinfunction "2_2") (pintype "passive"))
      (node (ref "C7") (pin "2") (pinfunction "2_2") (pintype "passive"))
      (node (ref "C70") (pin "2") (pinfunction "2_2") (pintype "passive"))
      (node (ref "C8") (pin "2") (pinfunction "2_2") (pintype "passive"))
      (node (ref "C9") (pin "2") (pinfunction "2_2") (pintype "passive"))
      (node (ref "CH2") (pin "1") (pinfunction "GND_1") (pintype "bidirectional"))
      (node (ref "IC1") (pin "1") (pinfunction "GND_1") (pintype "input"))
      (node (ref "IC3") (pin "13") (pinfunction "GND_13") (pintype "power_in"))
      (node (ref "IC3") (pin "23") (pinfunction "GND_23") (pintype "power_in"))
      (node (ref "IC3") (pin "3") (pinfunction "AGND_3") (pintype "power_in"))
      (node (ref "IC3") (pin "33") (pinfunction "GND_33") (pintype "power_in"))
      (node (ref "IC3") (pin "43") (pinfunction "GND_43") (pintype "power_in"))
      (node (ref "IC3") (pin "53") (pinfunction "GND_53") (pintype "power_in"))
      (node (ref "IC3") (pin "63") (pinfunction "GND_63") (pintype "power_in"))
      (node (ref "IC3") (pin "73") (pinfunction "GND_73") (pintype "power_in"))
      (node (ref "IC3") (pin "84") (pinfunction "GND_84") (pintype "power_in"))
      (node (ref "IC3") (pin "93") (pinfunction "AGND_93") (pintype "power_in"))
      (node (ref "JP10") (pin "13") (pinfunction "13_13") (pintype "passive"))
      (node (ref "JP10") (pin "23") (pinfunction "23_23") (pintype "passive"))
      (node (ref "JP10") (pin "3") (pinfunction "3_3") (pintype "passive"))
      (node (ref "JP11") (pin "18") (pinfunction "18_18") (pintype "passive"))
      (node (ref "JP11") (pin "8") (pinfunction "8_8") (pintype "passive"))
      (node (ref "JP12") (pin "13") (pinfunction "13_13") (pintype "passive"))
      (node (ref "JP12") (pin "23") (pinfunction "23_23") (pintype "passive"))
      (node (ref "JP12") (pin "3") (pinfunction "3_3") (pintype "passive"))
      (node (ref "JP13") (pin "18") (pinfunction "18_18") (pintype "passive"))
      (node (ref "JP13") (pin "8") (pinfunction "8_8") (pintype "passive"))
      (node (ref "JP14") (pin "13") (pinfunction "13_13") (pintype "passive"))
      (node (ref "JP14") (pin "23") (pinfunction "23_23") (pintype "passive"))
      (node (ref "JP14") (pin "3") (pinfunction "3_3") (pintype "passive"))
      (node (ref "JP15") (pin "18") (pinfunction "18_18") (pintype "passive"))
      (node (ref "JP15") (pin "8") (pinfunction "8_8") (pintype "passive"))
      (node (ref "JP16") (pin "13") (pinfunction "13_13") (pintype "passive"))
      (node (ref "JP16") (pin "23") (pinfunction "23_23") (pintype "passive"))
      (node (ref "JP16") (pin "3") (pinfunction "3_3") (pintype "passive"))
      (node (ref "JP17") (pin "18") (pinfunction "18_18") (pintype "passive"))
      (node (ref "JP17") (pin "8") (pinfunction "8_8") (pintype "passive"))
      (node (ref "JP2") (pin "1") (pinfunction "1_1") (pintype "passive"))
      (node (ref "JP2") (pin "11") (pinfunction "11_11") (pintype "passive"))
      (node (ref "JP2") (pin "13") (pinfunction "13_13") (pintype "passive"))
      (node (ref "JP2") (pin "15") (pinfunction "15_15") (pintype "passive"))
      (node (ref "JP2") (pin "17") (pinfunction "17_17") (pintype "passive"))
      (node (ref "JP2") (pin "19") (pinfunction "19_19") (pintype "passive"))
      (node (ref "JP2") (pin "21") (pinfunction "21_21") (pintype "passive"))
      (node (ref "JP2") (pin "23") (pinfunction "23_23") (pintype "passive"))
      (node (ref "JP2") (pin "25") (pinfunction "25_25") (pintype "passive"))
      (node (ref "JP2") (pin "27") (pinfunction "27_27") (pintype "passive"))
      (node (ref "JP2") (pin "29") (pinfunction "29_29") (pintype "passive"))
      (node (ref "JP2") (pin "3") (pinfunction "3_3") (pintype "passive"))
      (node (ref "JP2") (pin "31") (pinfunction "31_31") (pintype "passive"))
      (node (ref "JP2") (pin "33") (pinfunction "33_33") (pintype "passive"))
      (node (ref "JP2") (pin "35") (pinfunction "35_35") (pintype "passive"))
      (node (ref "JP2") (pin "37") (pinfunction "37_37") (pintype "passive"))
      (node (ref "JP2") (pin "39") (pinfunction "39_39") (pintype "passive"))
      (node (ref "JP2") (pin "41") (pinfunction "41_41") (pintype "passive"))
      (node (ref "JP2") (pin "43") (pinfunction "43_43") (pintype "passive"))
      (node (ref "JP2") (pin "45") (pinfunction "45_45") (pintype "passive"))
      (node (ref "JP2") (pin "47") (pinfunction "47_47") (pintype "passive"))
      (node (ref "JP2") (pin "49") (pinfunction "49_49") (pintype "passive"))
      (node (ref "JP2") (pin "5") (pinfunction "5_5") (pintype "passive"))
      (node (ref "JP2") (pin "7") (pinfunction "7_7") (pintype "passive"))
      (node (ref "JP2") (pin "9") (pinfunction "9_9") (pintype "passive"))
      (node (ref "JP3") (pin "1") (pinfunction "1_1") (pintype "passive"))
      (node (ref "JP3") (pin "11") (pinfunction "11_11") (pintype "passive"))
      (node (ref "JP3") (pin "13") (pinfunction "13_13") (pintype "passive"))
      (node (ref "JP3") (pin "15") (pinfunction "15_15") (pintype "passive"))
      (node (ref "JP3") (pin "17") (pinfunction "17_17") (pintype "passive"))
      (node (ref "JP3") (pin "19") (pinfunction "19_19") (pintype "passive"))
      (node (ref "JP3") (pin "21") (pinfunction "21_21") (pintype "passive"))
      (node (ref "JP3") (pin "23") (pinfunction "23_23") (pintype "passive"))
      (node (ref "JP3") (pin "25") (pinfunction "25_25") (pintype "passive"))
      (node (ref "JP3") (pin "27") (pinfunction "27_27") (pintype "passive"))
      (node (ref "JP3") (pin "29") (pinfunction "29_29") (pintype "passive"))
      (node (ref "JP3") (pin "3") (pinfunction "3_3") (pintype "passive"))
      (node (ref "JP3") (pin "31") (pinfunction "31_31") (pintype "passive"))
      (node (ref "JP3") (pin "33") (pinfunction "33_33") (pintype "passive"))
      (node (ref "JP3") (pin "35") (pinfunction "35_35") (pintype "passive"))
      (node (ref "JP3") (pin "37") (pinfunction "37_37") (pintype "passive"))
      (node (ref "JP3") (pin "39") (pinfunction "39_39") (pintype "passive"))
      (node (ref "JP3") (pin "41") (pinfunction "41_41") (pintype "passive"))
      (node (ref "JP3") (pin "43") (pinfunction "43_43") (pintype "passive"))
      (node (ref "JP3") (pin "45") (pinfunction "45_45") (pintype "passive"))
      (node (ref "JP3") (pin "47") (pinfunction "47_47") (pintype "passive"))
      (node (ref "JP3") (pin "49") (pinfunction "49_49") (pintype "passive"))
      (node (ref "JP3") (pin "5") (pinfunction "5_5") (pintype "passive"))
      (node (ref "JP3") (pin "7") (pinfunction "7_7") (pintype "passive"))
      (node (ref "JP3") (pin "9") (pinfunction "9_9") (pintype "passive"))
      (node (ref "JP4") (pin "1") (pinfunction "1_1") (pintype "passive"))
      (node (ref "JP4") (pin "11") (pinfunction "11_11") (pintype "passive"))
      (node (ref "JP4") (pin "13") (pinfunction "13_13") (pintype "passive"))
      (node (ref "JP4") (pin "15") (pinfunction "15_15") (pintype "passive"))
      (node (ref "JP4") (pin "17") (pinfunction "17_17") (pintype "passive"))
      (node (ref "JP4") (pin "19") (pinfunction "19_19") (pintype "passive"))
      (node (ref "JP4") (pin "21") (pinfunction "21_21") (pintype "passive"))
      (node (ref "JP4") (pin "23") (pinfunction "23_23") (pintype "passive"))
      (node (ref "JP4") (pin "25") (pinfunction "25_25") (pintype "passive"))
      (node (ref "JP4") (pin "27") (pinfunction "27_27") (pintype "passive"))
      (node (ref "JP4") (pin "29") (pinfunction "29_29") (pintype "passive"))
      (node (ref "JP4") (pin "3") (pinfunction "3_3") (pintype "passive"))
      (node (ref "JP4") (pin "31") (pinfunction "31_31") (pintype "passive"))
      (node (ref "JP4") (pin "33") (pinfunction "33_33") (pintype "passive"))
      (node (ref "JP4") (pin "35") (pinfunction "35_35") (pintype "passive"))
      (node (ref "JP4") (pin "37") (pinfunction "37_37") (pintype "passive"))
      (node (ref "JP4") (pin "39") (pinfunction "39_39") (pintype "passive"))
      (node (ref "JP4") (pin "41") (pinfunction "41_41") (pintype "passive"))
      (node (ref "JP4") (pin "43") (pinfunction "43_43") (pintype "passive"))
      (node (ref "JP4") (pin "45") (pinfunction "45_45") (pintype "passive"))
      (node (ref "JP4") (pin "47") (pinfunction "47_47") (pintype "passive"))
      (node (ref "JP4") (pin "49") (pinfunction "49_49") (pintype "passive"))
      (node (ref "JP4") (pin "5") (pinfunction "5_5") (pintype "passive"))
      (node (ref "JP4") (pin "7") (pinfunction "7_7") (pintype "passive"))
      (node (ref "JP4") (pin "9") (pinfunction "9_9") (pintype "passive"))
      (node (ref "JP5") (pin "1") (pinfunction "1_1") (pintype "passive"))
      (node (ref "JP6") (pin "2") (pinfunction "2_2") (pintype "passive"))
      (node (ref "JP7") (pin "2") (pinfunction "2_2") (pintype "passive"))
      (node (ref "JP8") (pin "2") (pinfunction "2_2") (pintype "passive"))
      (node (ref "JP9") (pin "1") (pinfunction "1_1") (pintype "passive"))
      (node (ref "JP9") (pin "11") (pinfunction "11_11") (pintype "passive"))
      (node (ref "JP9") (pin "13") (pinfunction "13_13") (pintype "passive"))
      (node (ref "JP9") (pin "15") (pinfunction "15_15") (pintype "passive"))
      (node (ref "JP9") (pin "17") (pinfunction "17_17") (pintype "passive"))
      (node (ref "JP9") (pin "19") (pinfunction "19_19") (pintype "passive"))
      (node (ref "JP9") (pin "21") (pinfunction "21_21") (pintype "passive"))
      (node (ref "JP9") (pin "23") (pinfunction "23_23") (pintype "passive"))
      (node (ref "JP9") (pin "25") (pinfunction "25_25") (pintype "passive"))
      (node (ref "JP9") (pin "27") (pinfunction "27_27") (pintype "passive"))
      (node (ref "JP9") (pin "29") (pinfunction "29_29") (pintype "passive"))
      (node (ref "JP9") (pin "3") (pinfunction "3_3") (pintype "passive"))
      (node (ref "JP9") (pin "31") (pinfunction "31_31") (pintype "passive"))
      (node (ref "JP9") (pin "33") (pinfunction "33_33") (pintype "passive"))
      (node (ref "JP9") (pin "35") (pinfunction "35_35") (pintype "passive"))
      (node (ref "JP9") (pin "37") (pinfunction "37_37") (pintype "passive"))
      (node (ref "JP9") (pin "39") (pinfunction "39_39") (pintype "passive"))
      (node (ref "JP9") (pin "41") (pinfunction "41_41") (pintype "passive"))
      (node (ref "JP9") (pin "43") (pinfunction "43_43") (pintype "passive"))
      (node (ref "JP9") (pin "45") (pinfunction "45_45") (pintype "passive"))
      (node (ref "JP9") (pin "47") (pinfunction "47_47") (pintype "passive"))
      (node (ref "JP9") (pin "49") (pinfunction "49_49") (pintype "passive"))
      (node (ref "JP9") (pin "5") (pinfunction "5_5") (pintype "passive"))
      (node (ref "JP9") (pin "7") (pinfunction "7_7") (pintype "passive"))
      (node (ref "JP9") (pin "9") (pinfunction "9_9") (pintype "passive"))
      (node (ref "MAX1") (pin "5") (pinfunction "GND_5") (pintype "bidirectional"))
      (node (ref "Q4") (pin "4") (pinfunction "G_4") (pintype "passive"))
      (node (ref "Q7") (pin "2") (pinfunction "S_2") (pintype "passive"))
      (node (ref "R11") (pin "1") (pinfunction "1_1") (pintype "passive"))
      (node (ref "R12") (pin "1") (pinfunction "1_1") (pintype "passive"))
      (node (ref "R14") (pin "1") (pinfunction "1_1") (pintype "passive"))
      (node (ref "R15") (pin "1") (pinfunction "1_1") (pintype "passive"))
      (node (ref "R17") (pin "2") (pinfunction "2_2") (pintype "passive"))
      (node (ref "R50") (pin "2") (pinfunction "2_2") (pintype "passive"))
      (node (ref "R52") (pin "2") (pinfunction "2_2") (pintype "passive"))
      (node (ref "R7") (pin "1") (pinfunction "1_1") (pintype "passive"))
      (node (ref "R9") (pin "1") (pinfunction "1_1") (pintype "passive"))
      (node (ref "SW1") (pin "1") (pinfunction "S_1") (pintype "passive"))
      (node (ref "SW1") (pin "2") (pinfunction "S1_2") (pintype "passive"))
      (node (ref "SW2") (pin "1") (pinfunction "S_1") (pintype "passive"))
      (node (ref "SW2") (pin "2") (pinfunction "S1_2") (pintype "passive"))
      (node (ref "U$1") (pin "4") (pinfunction "GND_4") (pintype "power_in"))
      (node (ref "U$2") (pin "16") (pinfunction "GND_16") (pintype "bidirectional"))
      (node (ref "U$2") (pin "17") (pinfunction "GND_17") (pintype "bidirectional"))
      (node (ref "U$2") (pin "24") (pinfunction "GND_24") (pintype "bidirectional"))
      (node (ref "U$2") (pin "25") (pinfunction "GND_25") (pintype "bidirectional"))
      (node (ref "U$3") (pin "17") (pinfunction "GND_17") (pintype "bidirectional"))
      (node (ref "U$3") (pin "3") (pinfunction "GND_3") (pintype "bidirectional"))
      (node (ref "U$6") (pin "16") (pinfunction "GND_16") (pintype "bidirectional"))
      (node (ref "U$6") (pin "17") (pinfunction "GND_17") (pintype "bidirectional"))
      (node (ref "U$6") (pin "24") (pinfunction "GND_24") (pintype "bidirectional"))
      (node (ref "U$6") (pin "25") (pinfunction "GND_25") (pintype "bidirectional"))
      (node (ref "X2") (pin "1") (pinfunction "KL_1") (pintype "passive"))
      (node (ref "X4") (pin "5") (pinfunction "GND_5") (pintype "passive"))
    )
    (net (code "12") (name "INA-0") (class "Default")
      (node (ref "IC3") (pin "30") (pinfunction "PD5_30") (pintype "bidirectional"))
      (node (ref "JP11") (pin "5") (pinfunction "5_5") (pintype "passive"))
      (node (ref "JP15") (pin "5") (pinfunction "5_5") (pintype "passive"))
      (node (ref "U$2") (pin "7") (pinfunction "IN-A_7") (pintype "bidirectional"))
    )
    (net (code "13") (name "INA-1") (class "Default")
      (node (ref "IC3") (pin "26") (pinfunction "PD1_26") (pintype "bidirectional"))
      (node (ref "JP11") (pin "1") (pinfunction "1_1") (pintype "passive"))
      (node (ref "JP15") (pin "1") (pinfunction "1_1") (pintype "passive"))
      (node (ref "U$6") (pin "7") (pinfunction "IN-A_7") (pintype "bidirectional"))
    )
    (net (code "14") (name "INB-0") (class "Default")
      (node (ref "IC3") (pin "29") (pinfunction "PD4_29") (pintype "bidirectional"))
      (node (ref "JP11") (pin "4") (pinfunction "4_4") (pintype "passive"))
      (node (ref "JP15") (pin "4") (pinfunction "4_4") (pintype "passive"))
      (node (ref "U$2") (pin "8") (pinfunction "IN-B_8") (pintype "bidirectional"))
    )
    (net (code "15") (name "INB-1") (class "Default")
      (node (ref "IC3") (pin "25") (pinfunction "PD0_25") (pintype "bidirectional"))
      (node (ref "JP10") (pin "25") (pinfunction "25_25") (pintype "passive"))
      (node (ref "JP14") (pin "25") (pinfunction "25_25") (pintype "passive"))
      (node (ref "U$6") (pin "8") (pinfunction "IN-B_8") (pintype "bidirectional"))
    )
    (net (code "16") (name "IPROPI-0A") (class "Default")
      (node (ref "IC3") (pin "6") (pinfunction "PB1_6") (pintype "bidirectional"))
      (node (ref "IC3") (pin "96") (pinfunction "PA1_96") (pintype "bidirectional"))
      (node (ref "JP10") (pin "6") (pinfunction "6_6") (pintype "passive"))
      (node (ref "JP13") (pin "21") (pinfunction "21_21") (pintype "passive"))
      (node (ref "JP14") (pin "6") (pinfunction "6_6") (pintype "passive"))
      (node (ref "JP17") (pin "21") (pinfunction "21_21") (pintype "passive"))
      (node (ref "R12") (pin "2") (pinfunction "2_2") (pintype "passive"))
      (node (ref "U$2") (pin "10") (pinfunction "IPROPI-A_10") (pintype "bidirectional"))
    )
    (net (code "17") (name "IPROPI-0B") (class "Default")
      (node (ref "IC3") (pin "5") (pinfunction "PB0_5") (pintype "bidirectional"))
      (node (ref "IC3") (pin "95") (pinfunction "PA0_95") (pintype "bidirectional"))
      (node (ref "JP10") (pin "5") (pinfunction "5_5") (pintype "passive"))
      (node (ref "JP13") (pin "20") (pinfunction "20_20") (pintype "passive"))
      (node (ref "JP14") (pin "5") (pinfunction "5_5") (pintype "passive"))
      (node (ref "JP17") (pin "20") (pinfunction "20_20") (pintype "passive"))
      (node (ref "R11") (pin "2") (pinfunction "2_2") (pintype "passive"))
      (node (ref "U$2") (pin "12") (pinfunction "IPROPI-B_12") (pintype "bidirectional"))
    )
    (net (code "18") (name "IPROPI-1A") (class "Default")
      (node (ref "R15") (pin "2") (pinfunction "2_2") (pintype "passive"))
      (node (ref "U$6") (pin "10") (pinfunction "IPROPI-A_10") (pintype "bidirectional"))
    )
    (net (code "19") (name "IPROPI-1B") (class "Default")
      (node (ref "R14") (pin "2") (pinfunction "2_2") (pintype "passive"))
      (node (ref "U$6") (pin "12") (pinfunction "IPROPI-B_12") (pintype "bidirectional"))
    )
    (net (code "20") (name "LED0") (class "Default")
      (node (ref "IC3") (pin "55") (pinfunction "PH0_55") (pintype "bidirectional"))
    )
    (net (code "21") (name "LED1") (class "Default")
      (node (ref "IC3") (pin "56") (pinfunction "PH1_56") (pintype "bidirectional"))
    )
    (net (code "22") (name "LED2") (class "Default")
      (node (ref "IC3") (pin "57") (pinfunction "PH2_57") (pintype "bidirectional"))
    )
    (net (code "23") (name "LED3") (class "Default")
      (node (ref "IC3") (pin "58") (pinfunction "PH3_58") (pintype "bidirectional"))
    )
    (net (code "24") (name "MISO") (class "Default")
      (node (ref "IC3") (pin "21") (pinfunction "PC6_21") (pintype "bidirectional"))
      (node (ref "JP10") (pin "21") (pinfunction "21_21") (pintype "passive"))
      (node (ref "JP14") (pin "21") (pinfunction "21_21") (pintype "passive"))
      (node (ref "U$2") (pin "3") (pinfunction "SDO_3") (pintype "bidirectional"))
      (node (ref "U$6") (pin "3") (pinfunction "SDO_3") (pintype "bidirectional"))
    )
    (net (code "25") (name "MODE_485") (class "Default")
      (node (ref "IC3") (pin "40") (pinfunction "PE5_40") (pintype "bidirectional"))
      (node (ref "MAX1") (pin "2") (pinfunction "RE/_2") (pintype "input"))
      (node (ref "MAX1") (pin "3") (pinfunction "DE_3") (pintype "input"))
      (node (ref "R52") (pin "1") (pinfunction "1_1") (pintype "passive"))
    )
    (net (code "26") (name "MOSI") (class "Default")
      (node (ref "IC3") (pin "20") (pinfunction "PC5_20") (pintype "bidirectional"))
      (node (ref "JP10") (pin "20") (pinfunction "20_20") (pintype "passive"))
      (node (ref "JP14") (pin "20") (pinfunction "20_20") (pintype "passive"))
      (node (ref "U$2") (pin "4") (pinfunction "SDI_4") (pintype "bidirectional"))
      (node (ref "U$6") (pin "4") (pinfunction "SDI_4") (pintype "bidirectional"))
    )
    (net (code "27") (name "NFAUL-0") (class "Default")
      (node (ref "IC3") (pin "32") (pinfunction "PD7_32") (pintype "bidirectional"))
      (node (ref "JP11") (pin "7") (pinfunction "7_7") (pintype "passive"))
      (node (ref "JP15") (pin "7") (pinfunction "7_7") (pintype "passive"))
      (node (ref "R13") (pin "1") (pinfunction "1_1") (pintype "passive"))
      (node (ref "U$2") (pin "2") (pinfunction "FAOU_2") (pintype "bidirectional"))
    )
    (net (code "28") (name "NFAUL-1") (class "Default")
      (node (ref "IC3") (pin "28") (pinfunction "PD3_28") (pintype "bidirectional"))
      (node (ref "JP11") (pin "3") (pinfunction "3_3") (pintype "passive"))
      (node (ref "JP15") (pin "3") (pinfunction "3_3") (pintype "passive"))
      (node (ref "R16") (pin "1") (pinfunction "1_1") (pintype "passive"))
      (node (ref "U$6") (pin "2") (pinfunction "FAOU_2") (pintype "bidirectional"))
    )
    (net (code "29") (name "NSLEEP-0") (class "Default")
      (node (ref "IC3") (pin "31") (pinfunction "PD6_31") (pintype "bidirectional"))
      (node (ref "JP11") (pin "6") (pinfunction "6_6") (pintype "passive"))
      (node (ref "JP15") (pin "6") (pinfunction "6_6") (pintype "passive"))
      (node (ref "U$2") (pin "11") (pinfunction "NSLEEP_11") (pintype "bidirectional"))
    )
    (net (code "30") (name "NSLEEP-1") (class "Default")
      (node (ref "IC3") (pin "27") (pinfunction "PD2_27") (pintype "bidirectional"))
      (node (ref "JP11") (pin "2") (pinfunction "2_2") (pintype "passive"))
      (node (ref "JP15") (pin "2") (pinfunction "2_2") (pintype "passive"))
      (node (ref "U$6") (pin "11") (pinfunction "NSLEEP_11") (pintype "bidirectional"))
    )
    (net (code "31") (name "Net-(JP1-Pad2)") (class "Default")
      (node (ref "JP1") (pin "2") (pinfunction "2_2") (pintype "passive"))
      (node (ref "R1") (pin "1") (pinfunction "1_1") (pintype "passive"))
    )
    (net (code "32") (name "Net-(MAX1-RO)") (class "Default")
      (node (ref "MAX1") (pin "1") (pinfunction "RO_1") (pintype "output"))
      (node (ref "Q10") (pin "3") (pinfunction "D_3") (pintype "passive"))
    )
    (net (code "33") (name "Net-(Q8-D)") (class "Default")
      (node (ref "Q8") (pin "3") (pinfunction "D_3") (pintype "passive"))
      (node (ref "R8") (pin "2") (pinfunction "2_2") (pintype "passive"))
      (node (ref "U$1") (pin "1") (pinfunction "SWC_1") (pintype "input"))
      (node (ref "U$1") (pin "7") (pinfunction "IPK_7") (pintype "bidirectional"))
      (node (ref "U$1") (pin "8") (pinfunction "DC_8") (pintype "input"))
    )
    (net (code "34") (name "Net-(Q8-G)") (class "Default")
      (node (ref "Q8") (pin "1") (pinfunction "G_1") (pintype "passive"))
      (node (ref "R7") (pin "2") (pinfunction "2_2") (pintype "passive"))
      (node (ref "U$1") (pin "2") (pinfunction "SWE_2") (pintype "input"))
    )
    (net (code "35") (name "Net-(Q8-S)") (class "Default")
      (node (ref "L2") (pin "1") (pinfunction "1_1") (pintype "passive"))
      (node (ref "Q8") (pin "2") (pinfunction "S_2") (pintype "passive"))
    )
    (net (code "36") (name "Net-(R48-Pad1)") (class "Default")
      (node (ref "R48") (pin "1") (pinfunction "1_1") (pintype "passive"))
      (node (ref "SJ1") (pin "1") (pinfunction "1_1") (pintype "passive"))
    )
    (net (code "37") (name "Net-(U$1-COMP)") (class "Default")
      (node (ref "R10") (pin "2") (pinfunction "2_2") (pintype "passive"))
      (node (ref "R9") (pin "2") (pinfunction "2_2") (pintype "passive"))
      (node (ref "U$1") (pin "5") (pinfunction "COMP_5") (pintype "input"))
    )
    (net (code "38") (name "Net-(U$1-TC)") (class "Default")
      (node (ref "C11") (pin "1") (pinfunction "1_1") (pintype "passive"))
      (node (ref "U$1") (pin "3") (pinfunction "TC_3") (pintype "input"))
    )
    (net (code "39") (name "Net-(U$2-CPH)") (class "Default")
      (node (ref "C27") (pin "1") (pinfunction "1_1") (pintype "passive"))
      (node (ref "U$2") (pin "22") (pinfunction "CPH_22") (pintype "bidirectional"))
    )
    (net (code "40") (name "Net-(U$2-CPL)") (class "Default")
      (node (ref "C27") (pin "2") (pinfunction "2_2") (pintype "passive"))
      (node (ref "U$2") (pin "23") (pinfunction "CPL_23") (pintype "bidirectional"))
    )
    (net (code "41") (name "Net-(U$2-VCP)") (class "Default")
      (node (ref "C29") (pin "2") (pinfunction "2_2") (pintype "passive"))
      (node (ref "U$2") (pin "21") (pinfunction "VCP_21") (pintype "bidirectional"))
    )
    (net (code "42") (name "Net-(U$3-CPI)") (class "Default")
      (node (ref "C15") (pin "2") (pinfunction "2_2") (pintype "passive"))
      (node (ref "U$3") (pin "5") (pinfunction "CPI_5") (pintype "bidirectional"))
    )
    (net (code "43") (name "Net-(U$3-CPO)") (class "Default")
      (node (ref "C15") (pin "1") (pinfunction "1_1") (pintype "passive"))
      (node (ref "U$3") (pin "4") (pinfunction "CPO_4") (pintype "bidirectional"))
    )
    (net (code "44") (name "Net-(U$3-VCP)") (class "Default")
      (node (ref "C13") (pin "2") (pinfunction "2_2") (pintype "passive"))
      (node (ref "U$3") (pin "6") (pinfunction "VCP_6") (pintype "bidirectional"))
    )
    (net (code "45") (name "Net-(U$6-CPH)") (class "Default")
      (node (ref "C31") (pin "1") (pinfunction "1_1") (pintype "passive"))
      (node (ref "U$6") (pin "22") (pinfunction "CPH_22") (pintype "bidirectional"))
    )
    (net (code "46") (name "Net-(U$6-CPL)") (class "Default")
      (node (ref "C31") (pin "2") (pinfunction "2_2") (pintype "passive"))
      (node (ref "U$6") (pin "23") (pinfunction "CPL_23") (pintype "bidirectional"))
    )
    (net (code "47") (name "Net-(U$6-VCP)") (class "Default")
      (node (ref "C33") (pin "2") (pinfunction "2_2") (pintype "passive"))
      (node (ref "U$6") (pin "21") (pinfunction "VCP_21") (pintype "bidirectional"))
    )
    (net (code "48") (name "Net-(X5A-KL)") (class "Default")
      (node (ref "U$2") (pin "14") (pinfunction "OUT-B_14") (pintype "bidirectional"))
      (node (ref "U$2") (pin "15") (pinfunction "OUT-B_15") (pintype "bidirectional"))
      (node (ref "X5") (pin "1") (pinfunction "KL_1") (pintype "passive"))
    )
    (net (code "49") (name "Net-(X5B-KL)") (class "Default")
      (node (ref "U$2") (pin "18") (pinfunction "OUT-A_18") (pintype "bidirectional"))
      (node (ref "U$2") (pin "19") (pinfunction "OUT-A_19") (pintype "bidirectional"))
      (node (ref "X5") (pin "2") (pinfunction "KL_2") (pintype "passive"))
    )
    (net (code "50") (name "Net-(X6A-KL)") (class "Default")
      (node (ref "U$6") (pin "14") (pinfunction "OUT-B_14") (pintype "bidirectional"))
      (node (ref "U$6") (pin "15") (pinfunction "OUT-B_15") (pintype "bidirectional"))
      (node (ref "X6") (pin "1") (pinfunction "KL_1") (pintype "passive"))
    )
    (net (code "51") (name "Net-(X6B-KL)") (class "Default")
      (node (ref "U$6") (pin "18") (pinfunction "OUT-A_18") (pintype "bidirectional"))
      (node (ref "U$6") (pin "19") (pinfunction "OUT-A_19") (pintype "bidirectional"))
      (node (ref "X6") (pin "2") (pinfunction "KL_2") (pintype "passive"))
    )
    (net (code "52") (name "OFF") (class "Default")
      (node (ref "C37") (pin "2") (pinfunction "2_2") (pintype "passive"))
      (node (ref "IC3") (pin "72") (pinfunction "PJ7_72") (pintype "bidirectional"))
      (node (ref "JP1") (pin "3") (pinfunction "3_3") (pintype "passive"))
      (node (ref "JP8") (pin "1") (pinfunction "1_1") (pintype "passive"))
      (node (ref "Q7") (pin "1") (pinfunction "G_1") (pintype "passive"))
      (node (ref "R1") (pin "2") (pinfunction "2_2") (pintype "passive"))
      (node (ref "R17") (pin "1") (pinfunction "1_1") (pintype "passive"))
      (node (ref "SW2") (pin "3") (pinfunction "P_3") (pintype "passive"))
      (node (ref "SW2") (pin "4") (pinfunction "P1_4") (pintype "passive"))
    )
    (net (code "53") (name "ON") (class "Default")
      (node (ref "C12") (pin "2") (pinfunction "2_2") (pintype "passive"))
      (node (ref "JP7") (pin "1") (pinfunction "1_1") (pintype "passive"))
      (node (ref "R6") (pin "2") (pinfunction "2_2") (pintype "passive"))
      (node (ref "SW1") (pin "3") (pinfunction "P_3") (pintype "passive"))
      (node (ref "SW1") (pin "4") (pinfunction "P1_4") (pintype "passive"))
    )
    (net (code "54") (name "PA2") (class "Default")
      (node (ref "IC3") (pin "97") (pinfunction "PA2_97") (pintype "bidirectional"))
      (node (ref "JP13") (pin "22") (pinfunction "22_22") (pintype "passive"))
      (node (ref "JP17") (pin "22") (pinfunction "22_22") (pintype "passive"))
    )
    (net (code "55") (name "PA3") (class "Default")
      (node (ref "IC3") (pin "98") (pinfunction "PA3_98") (pintype "bidirectional"))
      (node (ref "JP13") (pin "23") (pinfunction "23_23") (pintype "passive"))
      (node (ref "JP17") (pin "23") (pinfunction "23_23") (pintype "passive"))
    )
    (net (code "56") (name "PA4") (class "Default")
      (node (ref "IC3") (pin "99") (pinfunction "PA4_99") (pintype "bidirectional"))
      (node (ref "JP13") (pin "24") (pinfunction "24_24") (pintype "passive"))
      (node (ref "JP17") (pin "24") (pinfunction "24_24") (pintype "passive"))
    )
    (net (code "57") (name "PA5") (class "Default")
      (node (ref "IC3") (pin "100") (pinfunction "PA5_100") (pintype "bidirectional"))
      (node (ref "JP13") (pin "25") (pinfunction "25_25") (pintype "passive"))
      (node (ref "JP17") (pin "25") (pinfunction "25_25") (pintype "passive"))
    )
    (net (code "58") (name "PA6") (class "Default")
      (node (ref "IC3") (pin "1") (pinfunction "PA6_1") (pintype "bidirectional"))
      (node (ref "JP10") (pin "1") (pinfunction "1_1") (pintype "passive"))
      (node (ref "JP14") (pin "1") (pinfunction "1_1") (pintype "passive"))
    )
    (net (code "59") (name "PA7") (class "Default")
      (node (ref "IC3") (pin "2") (pinfunction "PA7_2") (pintype "bidirectional"))
      (node (ref "JP10") (pin "2") (pinfunction "2_2") (pintype "passive"))
      (node (ref "JP14") (pin "2") (pinfunction "2_2") (pintype "passive"))
    )
    (net (code "60") (name "PB2") (class "Default")
      (node (ref "IC3") (pin "7") (pinfunction "PB2_7") (pintype "bidirectional"))
      (node (ref "JP10") (pin "7") (pinfunction "7_7") (pintype "passive"))
      (node (ref "JP14") (pin "7") (pinfunction "7_7") (pintype "passive"))
    )
    (net (code "61") (name "PB3") (class "Default")
      (node (ref "IC3") (pin "8") (pinfunction "PB3_8") (pintype "bidirectional"))
      (node (ref "JP10") (pin "8") (pinfunction "8_8") (pintype "passive"))
      (node (ref "JP14") (pin "8") (pinfunction "8_8") (pintype "passive"))
    )
    (net (code "62") (name "PB4") (class "Default")
      (node (ref "IC3") (pin "9") (pinfunction "PB4_9") (pintype "bidirectional"))
      (node (ref "JP10") (pin "9") (pinfunction "9_9") (pintype "passive"))
      (node (ref "JP14") (pin "9") (pinfunction "9_9") (pintype "passive"))
    )
    (net (code "63") (name "PB5") (class "Default")
      (node (ref "IC3") (pin "10") (pinfunction "PB5_10") (pintype "bidirectional"))
      (node (ref "JP10") (pin "10") (pinfunction "10_10") (pintype "passive"))
      (node (ref "JP14") (pin "10") (pinfunction "10_10") (pintype "passive"))
    )
    (net (code "64") (name "PB6") (class "Default")
      (node (ref "IC3") (pin "11") (pinfunction "PB6_11") (pintype "bidirectional"))
      (node (ref "JP10") (pin "11") (pinfunction "11_11") (pintype "passive"))
      (node (ref "JP14") (pin "11") (pinfunction "11_11") (pintype "passive"))
    )
    (net (code "65") (name "PB7") (class "Default")
      (node (ref "IC3") (pin "12") (pinfunction "PB7_12") (pintype "bidirectional"))
      (node (ref "JP10") (pin "12") (pinfunction "12_12") (pintype "passive"))
      (node (ref "JP14") (pin "12") (pinfunction "12_12") (pintype "passive"))
    )
    (net (code "66") (name "PC0") (class "Default")
      (node (ref "IC3") (pin "15") (pinfunction "PC0_15") (pintype "bidirectional"))
      (node (ref "JP10") (pin "15") (pinfunction "15_15") (pintype "passive"))
      (node (ref "JP14") (pin "15") (pinfunction "15_15") (pintype "passive"))
    )
    (net (code "67") (name "PC1") (class "Default")
      (node (ref "IC3") (pin "16") (pinfunction "PC1_16") (pintype "bidirectional"))
      (node (ref "JP10") (pin "16") (pinfunction "16_16") (pintype "passive"))
      (node (ref "JP14") (pin "16") (pinfunction "16_16") (pintype "passive"))
    )
    (net (code "68") (name "PC2") (class "Default")
      (node (ref "IC3") (pin "17") (pinfunction "PC2_17") (pintype "bidirectional"))
      (node (ref "JP10") (pin "17") (pinfunction "17_17") (pintype "passive"))
      (node (ref "JP14") (pin "17") (pinfunction "17_17") (pintype "passive"))
    )
    (net (code "69") (name "PDI_DATA") (class "Default")
      (node (ref "IC3") (pin "89") (pinfunction "PDI_DATA_89") (pintype "bidirectional"))
      (node (ref "JP13") (pin "14") (pinfunction "14_14") (pintype "passive"))
      (node (ref "JP17") (pin "14") (pinfunction "14_14") (pintype "passive"))
      (node (ref "JP6") (pin "4") (pinfunction "4_4") (pintype "passive"))
    )
    (net (code "70") (name "PE0") (class "Default")
      (node (ref "IC3") (pin "35") (pinfunction "PE0_35") (pintype "bidirectional"))
      (node (ref "JP11") (pin "10") (pinfunction "10_10") (pintype "passive"))
      (node (ref "JP15") (pin "10") (pinfunction "10_10") (pintype "passive"))
    )
    (net (code "71") (name "PE1") (class "Default")
      (node (ref "IC3") (pin "36") (pinfunction "PE1_36") (pintype "bidirectional"))
      (node (ref "JP11") (pin "11") (pinfunction "11_11") (pintype "passive"))
      (node (ref "JP15") (pin "11") (pinfunction "11_11") (pintype "passive"))
    )
    (net (code "72") (name "PE2") (class "Default")
      (node (ref "IC3") (pin "37") (pinfunction "PE2_37") (pintype "bidirectional"))
      (node (ref "JP11") (pin "12") (pinfunction "12_12") (pintype "passive"))
      (node (ref "JP15") (pin "12") (pinfunction "12_12") (pintype "passive"))
    )
    (net (code "73") (name "PE3") (class "Default")
      (node (ref "IC3") (pin "38") (pinfunction "PE3_38") (pintype "bidirectional"))
      (node (ref "JP11") (pin "13") (pinfunction "13_13") (pintype "passive"))
      (node (ref "JP15") (pin "13") (pinfunction "13_13") (pintype "passive"))
    )
    (net (code "74") (name "PE4") (class "Default")
      (node (ref "IC3") (pin "39") (pinfunction "PE4_39") (pintype "bidirectional"))
      (node (ref "JP11") (pin "14") (pinfunction "14_14") (pintype "passive"))
      (node (ref "JP15") (pin "14") (pinfunction "14_14") (pintype "passive"))
    )
    (net (code "75") (name "PE5") (class "Default")
      (node (ref "JP11") (pin "15") (pinfunction "15_15") (pintype "passive"))
      (node (ref "JP15") (pin "15") (pinfunction "15_15") (pintype "passive"))
    )
    (net (code "76") (name "PF0") (class "Default")
      (node (ref "IC3") (pin "45") (pinfunction "PF0_45") (pintype "bidirectional"))
      (node (ref "JP11") (pin "20") (pinfunction "20_20") (pintype "passive"))
      (node (ref "JP15") (pin "20") (pinfunction "20_20") (pintype "passive"))
    )
    (net (code "77") (name "PF1") (class "Default")
      (node (ref "IC3") (pin "46") (pinfunction "PF1_46") (pintype "bidirectional"))
      (node (ref "JP11") (pin "21") (pinfunction "21_21") (pintype "passive"))
      (node (ref "JP15") (pin "21") (pinfunction "21_21") (pintype "passive"))
    )
    (net (code "78") (name "PF2") (class "Default")
      (node (ref "IC3") (pin "47") (pinfunction "PF2_47") (pintype "bidirectional"))
      (node (ref "JP11") (pin "22") (pinfunction "22_22") (pintype "passive"))
      (node (ref "JP15") (pin "22") (pinfunction "22_22") (pintype "passive"))
    )
    (net (code "79") (name "PF3") (class "Default")
      (node (ref "IC3") (pin "48") (pinfunction "PF3_48") (pintype "bidirectional"))
      (node (ref "JP11") (pin "23") (pinfunction "23_23") (pintype "passive"))
      (node (ref "JP15") (pin "23") (pinfunction "23_23") (pintype "passive"))
    )
    (net (code "80") (name "PF4") (class "Default")
      (node (ref "IC3") (pin "49") (pinfunction "PF4_49") (pintype "bidirectional"))
      (node (ref "JP11") (pin "24") (pinfunction "24_24") (pintype "passive"))
      (node (ref "JP15") (pin "24") (pinfunction "24_24") (pintype "passive"))
    )
    (net (code "81") (name "PF5") (class "Default")
      (node (ref "IC3") (pin "50") (pinfunction "PF5_50") (pintype "bidirectional"))
      (node (ref "JP11") (pin "25") (pinfunction "25_25") (pintype "passive"))
      (node (ref "JP15") (pin "25") (pinfunction "25_25") (pintype "passive"))
    )
    (net (code "82") (name "PH0") (class "Default")
      (node (ref "JP12") (pin "5") (pinfunction "5_5") (pintype "passive"))
      (node (ref "JP16") (pin "5") (pinfunction "5_5") (pintype "passive"))
    )
    (net (code "83") (name "PH1") (class "Default")
      (node (ref "JP12") (pin "6") (pinfunction "6_6") (pintype "passive"))
      (node (ref "JP16") (pin "6") (pinfunction "6_6") (pintype "passive"))
    )
    (net (code "84") (name "PH2") (class "Default")
      (node (ref "JP12") (pin "7") (pinfunction "7_7") (pintype "passive"))
      (node (ref "JP16") (pin "7") (pinfunction "7_7") (pintype "passive"))
    )
    (net (code "85") (name "PH3") (class "Default")
      (node (ref "JP12") (pin "8") (pinfunction "8_8") (pintype "passive"))
      (node (ref "JP16") (pin "8") (pinfunction "8_8") (pintype "passive"))
    )
    (net (code "86") (name "PH4") (class "Default")
      (node (ref "JP12") (pin "9") (pinfunction "9_9") (pintype "passive"))
      (node (ref "JP16") (pin "9") (pinfunction "9_9") (pintype "passive"))
    )
    (net (code "87") (name "PH5") (class "Default")
      (node (ref "JP12") (pin "10") (pinfunction "10_10") (pintype "passive"))
      (node (ref "JP16") (pin "10") (pinfunction "10_10") (pintype "passive"))
    )
    (net (code "88") (name "PH6") (class "Default")
      (node (ref "JP12") (pin "11") (pinfunction "11_11") (pintype "passive"))
      (node (ref "JP16") (pin "11") (pinfunction "11_11") (pintype "passive"))
    )
    (net (code "89") (name "PH7") (class "Default")
      (node (ref "JP12") (pin "12") (pinfunction "12_12") (pintype "passive"))
      (node (ref "JP16") (pin "12") (pinfunction "12_12") (pintype "passive"))
    )
    (net (code "90") (name "PJ0") (class "Default")
      (node (ref "IC3") (pin "65") (pinfunction "PJ0_65") (pintype "bidirectional"))
      (node (ref "JP12") (pin "15") (pinfunction "15_15") (pintype "passive"))
      (node (ref "JP16") (pin "15") (pinfunction "15_15") (pintype "passive"))
    )
    (net (code "91") (name "PJ1") (class "Default")
      (node (ref "IC3") (pin "66") (pinfunction "PJ1_66") (pintype "bidirectional"))
      (node (ref "JP12") (pin "16") (pinfunction "16_16") (pintype "passive"))
      (node (ref "JP16") (pin "16") (pinfunction "16_16") (pintype "passive"))
    )
    (net (code "92") (name "PJ2") (class "Default")
      (node (ref "IC3") (pin "67") (pinfunction "PJ2_67") (pintype "bidirectional"))
      (node (ref "JP12") (pin "17") (pinfunction "17_17") (pintype "passive"))
      (node (ref "JP16") (pin "17") (pinfunction "17_17") (pintype "passive"))
    )
    (net (code "93") (name "PJ3") (class "Default")
      (node (ref "IC3") (pin "68") (pinfunction "PJ3_68") (pintype "bidirectional"))
      (node (ref "JP12") (pin "18") (pinfunction "18_18") (pintype "passive"))
      (node (ref "JP16") (pin "18") (pinfunction "18_18") (pintype "passive"))
    )
    (net (code "94") (name "PJ4") (class "Default")
      (node (ref "IC3") (pin "69") (pinfunction "PJ4_69") (pintype "bidirectional"))
      (node (ref "JP12") (pin "19") (pinfunction "19_19") (pintype "passive"))
      (node (ref "JP16") (pin "19") (pinfunction "19_19") (pintype "passive"))
    )
    (net (code "95") (name "PJ5") (class "Default")
      (node (ref "IC3") (pin "70") (pinfunction "PJ5_70") (pintype "bidirectional"))
      (node (ref "JP12") (pin "20") (pinfunction "20_20") (pintype "passive"))
      (node (ref "JP16") (pin "20") (pinfunction "20_20") (pintype "passive"))
    )
    (net (code "96") (name "PJ6") (class "Default")
      (node (ref "IC3") (pin "71") (pinfunction "PJ6_71") (pintype "bidirectional"))
      (node (ref "JP12") (pin "21") (pinfunction "21_21") (pintype "passive"))
      (node (ref "JP16") (pin "21") (pinfunction "21_21") (pintype "passive"))
    )
    (net (code "97") (name "PJ7") (class "Default")
      (node (ref "JP12") (pin "22") (pinfunction "22_22") (pintype "passive"))
      (node (ref "JP16") (pin "22") (pinfunction "22_22") (pintype "passive"))
    )
    (net (code "98") (name "PK0") (class "Default")
      (node (ref "IC3") (pin "75") (pinfunction "PK0_75") (pintype "bidirectional"))
      (node (ref "JP12") (pin "25") (pinfunction "25_25") (pintype "passive"))
      (node (ref "JP16") (pin "25") (pinfunction "25_25") (pintype "passive"))
    )
    (net (code "99") (name "PK1") (class "Default")
      (node (ref "IC3") (pin "76") (pinfunction "PK1_76") (pintype "bidirectional"))
      (node (ref "JP13") (pin "1") (pinfunction "1_1") (pintype "passive"))
      (node (ref "JP17") (pin "1") (pinfunction "1_1") (pintype "passive"))
    )
    (net (code "100") (name "PK2") (class "Default")
      (node (ref "IC3") (pin "77") (pinfunction "PK2_77") (pintype "bidirectional"))
      (node (ref "JP13") (pin "2") (pinfunction "2_2") (pintype "passive"))
      (node (ref "JP17") (pin "2") (pinfunction "2_2") (pintype "passive"))
    )
    (net (code "101") (name "PK3") (class "Default")
      (node (ref "IC3") (pin "78") (pinfunction "PK3_78") (pintype "bidirectional"))
      (node (ref "JP13") (pin "3") (pinfunction "3_3") (pintype "passive"))
      (node (ref "JP17") (pin "3") (pinfunction "3_3") (pintype "passive"))
    )
    (net (code "102") (name "PK4") (class "Default")
      (node (ref "IC3") (pin "79") (pinfunction "PK4_79") (pintype "bidirectional"))
      (node (ref "JP13") (pin "4") (pinfunction "4_4") (pintype "passive"))
      (node (ref "JP17") (pin "4") (pinfunction "4_4") (pintype "passive"))
    )
    (net (code "103") (name "PK5") (class "Default")
      (node (ref "IC3") (pin "80") (pinfunction "PK5_80") (pintype "bidirectional"))
      (node (ref "JP13") (pin "5") (pinfunction "5_5") (pintype "passive"))
      (node (ref "JP17") (pin "5") (pinfunction "5_5") (pintype "passive"))
    )
    (net (code "104") (name "PK6") (class "Default")
      (node (ref "IC3") (pin "81") (pinfunction "PK6_81") (pintype "bidirectional"))
      (node (ref "JP13") (pin "6") (pinfunction "6_6") (pintype "passive"))
      (node (ref "JP17") (pin "6") (pinfunction "6_6") (pintype "passive"))
    )
    (net (code "105") (name "PK7") (class "Default")
      (node (ref "IC3") (pin "82") (pinfunction "PK7_82") (pintype "bidirectional"))
      (node (ref "JP13") (pin "7") (pinfunction "7_7") (pintype "passive"))
      (node (ref "JP17") (pin "7") (pinfunction "7_7") (pintype "passive"))
    )
    (net (code "106") (name "PQ0") (class "Default")
      (node (ref "IC3") (pin "85") (pinfunction "PQ0_85") (pintype "bidirectional"))
      (node (ref "JP13") (pin "10") (pinfunction "10_10") (pintype "passive"))
      (node (ref "JP17") (pin "10") (pinfunction "10_10") (pintype "passive"))
    )
    (net (code "107") (name "PQ1") (class "Default")
      (node (ref "IC3") (pin "86") (pinfunction "PQ1_86") (pintype "bidirectional"))
      (node (ref "JP13") (pin "11") (pinfunction "11_11") (pintype "passive"))
      (node (ref "JP17") (pin "11") (pinfunction "11_11") (pintype "passive"))
    )
    (net (code "108") (name "PQ2") (class "Default")
      (node (ref "IC3") (pin "87") (pinfunction "PQ2_87") (pintype "bidirectional"))
      (node (ref "JP13") (pin "12") (pinfunction "12_12") (pintype "passive"))
      (node (ref "JP17") (pin "12") (pinfunction "12_12") (pintype "passive"))
    )
    (net (code "109") (name "PQ3") (class "Default")
      (node (ref "IC3") (pin "88") (pinfunction "PQ3_88") (pintype "bidirectional"))
      (node (ref "JP13") (pin "13") (pinfunction "13_13") (pintype "passive"))
      (node (ref "JP17") (pin "13") (pinfunction "13_13") (pintype "passive"))
    )
    (net (code "110") (name "PR0") (class "Default")
      (node (ref "IC3") (pin "91") (pinfunction "PR0_91") (pintype "bidirectional"))
      (node (ref "JP13") (pin "16") (pinfunction "16_16") (pintype "passive"))
      (node (ref "JP17") (pin "16") (pinfunction "16_16") (pintype "passive"))
    )
    (net (code "111") (name "PR1") (class "Default")
      (node (ref "IC3") (pin "92") (pinfunction "PR1_92") (pintype "bidirectional"))
      (node (ref "JP13") (pin "17") (pinfunction "17_17") (pintype "passive"))
      (node (ref "JP17") (pin "17") (pinfunction "17_17") (pintype "passive"))
    )
    (net (code "112") (name "RESET") (class "Default")
      (node (ref "JP6") (pin "3") (pinfunction "3_3") (pintype "passive"))
    )
    (net (code "113") (name "RX") (class "Default")
      (node (ref "IC3") (pin "51") (pinfunction "PF6_51") (pintype "bidirectional"))
      (node (ref "JP12") (pin "1") (pinfunction "1_1") (pintype "passive"))
      (node (ref "JP16") (pin "1") (pinfunction "1_1") (pintype "passive"))
    )
    (net (code "114") (name "RXD0") (class "Default")
      (node (ref "CH2") (pin "2") (pinfunction "TX_2") (pintype "bidirectional"))
    )
    (net (code "115") (name "RX_485") (class "Default")
      (node (ref "IC3") (pin "41") (pinfunction "PE6_41") (pintype "bidirectional"))
      (node (ref "JP11") (pin "16") (pinfunction "16_16") (pintype "passive"))
      (node (ref "JP15") (pin "16") (pinfunction "16_16") (pintype "passive"))
      (node (ref "Q10") (pin "2") (pinfunction "S_2") (pintype "passive"))
      (node (ref "R51") (pin "1") (pinfunction "1_1") (pintype "passive"))
    )
    (net (code "116") (name "SCK") (class "Default")
      (node (ref "IC3") (pin "22") (pinfunction "PC7_22") (pintype "bidirectional"))
      (node (ref "JP10") (pin "22") (pinfunction "22_22") (pintype "passive"))
      (node (ref "JP14") (pin "22") (pinfunction "22_22") (pintype "passive"))
    )
    (net (code "117") (name "SCLK") (class "Default")
      (node (ref "U$2") (pin "5") (pinfunction "SCLK_5") (pintype "bidirectional"))
      (node (ref "U$6") (pin "5") (pinfunction "SCLK_5") (pintype "bidirectional"))
    )
    (net (code "118") (name "SS-0") (class "Default")
      (node (ref "IC3") (pin "18") (pinfunction "PC3_18") (pintype "bidirectional"))
      (node (ref "JP10") (pin "18") (pinfunction "18_18") (pintype "passive"))
      (node (ref "JP14") (pin "18") (pinfunction "18_18") (pintype "passive"))
      (node (ref "U$2") (pin "6") (pinfunction "SCS_6") (pintype "bidirectional"))
    )
    (net (code "119") (name "SS-1") (class "Default")
      (node (ref "IC3") (pin "19") (pinfunction "PC4_19") (pintype "bidirectional"))
      (node (ref "JP10") (pin "19") (pinfunction "19_19") (pintype "passive"))
      (node (ref "JP14") (pin "19") (pinfunction "19_19") (pintype "passive"))
      (node (ref "U$6") (pin "6") (pinfunction "SCS_6") (pintype "bidirectional"))
    )
    (net (code "120") (name "START_GATE1") (class "Default")
      (node (ref "C12") (pin "1") (pinfunction "1_1") (pintype "passive"))
      (node (ref "Q3") (pin "4") (pinfunction "G_4") (pintype "passive"))
      (node (ref "Q7") (pin "3") (pinfunction "D_3") (pintype "passive"))
      (node (ref "R5") (pin "2") (pinfunction "2_2") (pintype "passive"))
      (node (ref "R6") (pin "1") (pinfunction "1_1") (pintype "passive"))
    )
    (net (code "121") (name "SW0") (class "Default")
      (node (ref "IC3") (pin "62") (pinfunction "PH7_62") (pintype "bidirectional"))
    )
    (net (code "122") (name "SW1") (class "Default")
      (node (ref "IC3") (pin "61") (pinfunction "PH6_61") (pintype "bidirectional"))
    )
    (net (code "123") (name "SW2") (class "Default")
      (node (ref "IC3") (pin "60") (pinfunction "PH5_60") (pintype "bidirectional"))
    )
    (net (code "124") (name "SW3") (class "Default")
      (node (ref "IC3") (pin "59") (pinfunction "PH4_59") (pintype "bidirectional"))
    )
    (net (code "125") (name "TX") (class "Default")
      (node (ref "IC3") (pin "52") (pinfunction "PF7_52") (pintype "bidirectional"))
      (node (ref "JP12") (pin "2") (pinfunction "2_2") (pintype "passive"))
      (node (ref "JP16") (pin "2") (pinfunction "2_2") (pintype "passive"))
    )
    (net (code "126") (name "TXD0") (class "Default")
      (node (ref "CH2") (pin "3") (pinfunction "RX_3") (pintype "bidirectional"))
    )
    (net (code "127") (name "TX_485") (class "Default")
      (node (ref "IC3") (pin "42") (pinfunction "PE7_42") (pintype "bidirectional"))
      (node (ref "JP11") (pin "17") (pinfunction "17_17") (pintype "passive"))
      (node (ref "JP15") (pin "17") (pinfunction "17_17") (pintype "passive"))
      (node (ref "MAX1") (pin "4") (pinfunction "DI_4") (pintype "input"))
    )
    (net (code "128") (name "VCC") (class "Default")
      (node (ref "C13") (pin "1") (pinfunction "1_1") (pintype "passive"))
      (node (ref "C14") (pin "1") (pinfunction "1_1") (pintype "passive"))
      (node (ref "C16") (pin "1") (pinfunction "1_1") (pintype "passive"))
      (node (ref "C17") (pin "+") (pinfunction "+_+") (pintype "passive"))
      (node (ref "C28") (pin "1") (pinfunction "1_1") (pintype "passive"))
      (node (ref "C29") (pin "1") (pinfunction "1_1") (pintype "passive"))
      (node (ref "C32") (pin "1") (pinfunction "1_1") (pintype "passive"))
      (node (ref "C33") (pin "1") (pinfunction "1_1") (pintype "passive"))
      (node (ref "C38") (pin "+") (pinfunction "+_+") (pintype "passive"))
      (node (ref "C39") (pin "+") (pinfunction "+_+") (pintype "passive"))
      (node (ref "Q3") (pin "5") (pinfunction "D_5") (pintype "passive"))
      (node (ref "Q3") (pin "6") (pinfunction "D_6") (pintype "passive"))
      (node (ref "Q3") (pin "7") (pinfunction "D_7") (pintype "passive"))
      (node (ref "Q3") (pin "8") (pinfunction "D_8") (pintype "passive"))
      (node (ref "R8") (pin "1") (pinfunction "1_1") (pintype "passive"))
      (node (ref "U$1") (pin "6") (pinfunction "VCC_6") (pintype "power_in"))
      (node (ref "U$2") (pin "13") (pinfunction "VM_13") (pintype "bidirectional"))
      (node (ref "U$2") (pin "20") (pinfunction "VM_20") (pintype "bidirectional"))
      (node (ref "U$3") (pin "14") (pinfunction "VS_14") (pintype "bidirectional"))
      (node (ref "U$3") (pin "7") (pinfunction "VS_7") (pintype "bidirectional"))
      (node (ref "U$6") (pin "13") (pinfunction "VM_13") (pintype "bidirectional"))
      (node (ref "U$6") (pin "20") (pinfunction "VM_20") (pintype "bidirectional"))
    )
    (net (code "129") (name "unconnected-(CH2-.NC-Pad8)") (class "Default")
      (node (ref "CH2") (pin "8") (pinfunction ".NC_8") (pintype "bidirectional"))
    )
    (net (code "130") (name "unconnected-(CH2-CTS-Pad9)") (class "Default")
      (node (ref "CH2") (pin "9") (pinfunction "CTS_9") (pintype "bidirectional"))
    )
    (net (code "131") (name "unconnected-(CH2-DCD-Pad12)") (class "Default")
      (node (ref "CH2") (pin "12") (pinfunction "DCD_12") (pintype "bidirectional"))
    )
    (net (code "132") (name "unconnected-(CH2-DSR-Pad10)") (class "Default")
      (node (ref "CH2") (pin "10") (pinfunction "DSR_10") (pintype "bidirectional"))
    )
    (net (code "133") (name "unconnected-(CH2-DTR-Pad13)") (class "Default")
      (node (ref "CH2") (pin "13") (pinfunction "DTR_13") (pintype "bidirectional"))
    )
    (net (code "134") (name "unconnected-(CH2-NC-Pad7)") (class "Default")
      (node (ref "CH2") (pin "7") (pinfunction "NC_7") (pintype "bidirectional"))
    )
    (net (code "135") (name "unconnected-(CH2-RI-Pad11)") (class "Default")
      (node (ref "CH2") (pin "11") (pinfunction "RI_11") (pintype "bidirectional"))
    )
    (net (code "136") (name "unconnected-(CH2-RS232-Pad15)") (class "Default")
      (node (ref "CH2") (pin "15") (pinfunction "RS232_15") (pintype "bidirectional"))
    )
    (net (code "137") (name "unconnected-(U$3-5VOUT-Pad18)") (class "Default")
      (node (ref "U$3") (pin "18") (pinfunction "5VOUT_18") (pintype "bidirectional"))
    )
    (net (code "138") (name "unconnected-(U$3-BRA-Pad9)") (class "Default")
      (node (ref "U$3") (pin "9") (pinfunction "BRA_9") (pintype "bidirectional"))
    )
    (net (code "139") (name "unconnected-(U$3-BRB-Pad12)") (class "Default")
      (node (ref "U$3") (pin "12") (pinfunction "BRB_12") (pintype "bidirectional"))
    )
    (net (code "140") (name "unconnected-(U$3-CLK_IN-Pad27)") (class "Default")
      (node (ref "U$3") (pin "27") (pinfunction "CLK_IN_27") (pintype "bidirectional"))
    )
    (net (code "141") (name "unconnected-(U$3-DIAG-Pad21)") (class "Default")
      (node (ref "U$3") (pin "21") (pinfunction "DIAG_21") (pintype "bidirectional"))
    )
    (net (code "142") (name "unconnected-(U$3-DIE_PAD-PadPAD)") (class "Default")
      (node (ref "U$3") (pin "PAD") (pinfunction "DIE_PAD_PAD") (pintype "bidirectional"))
    )
    (net (code "143") (name "unconnected-(U$3-DIR-Pad23)") (class "Default")
      (node (ref "U$3") (pin "23") (pinfunction "DIR_23") (pintype "bidirectional"))
    )
    (net (code "144") (name "unconnected-(U$3-ENN-Pad24)") (class "Default")
      (node (ref "U$3") (pin "24") (pinfunction "ENN_24") (pintype "bidirectional"))
    )
    (net (code "145") (name "unconnected-(U$3-INDEX-Pad2)") (class "Default")
      (node (ref "U$3") (pin "2") (pinfunction "INDEX_2") (pintype "bidirectional"))
    )
    (net (code "146") (name "unconnected-(U$3-MS1-Pad28)") (class "Default")
      (node (ref "U$3") (pin "28") (pinfunction "MS1_28") (pintype "bidirectional"))
    )
    (net (code "147") (name "unconnected-(U$3-MS2-Pad1)") (class "Default")
      (node (ref "U$3") (pin "1") (pinfunction "MS2_1") (pintype "bidirectional"))
    )
    (net (code "148") (name "unconnected-(U$3-OA1-Pad10)") (class "Default")
      (node (ref "U$3") (pin "10") (pinfunction "OA1_10") (pintype "bidirectional"))
    )
    (net (code "149") (name "unconnected-(U$3-OA2-Pad8)") (class "Default")
      (node (ref "U$3") (pin "8") (pinfunction "OA2_8") (pintype "bidirectional"))
    )
    (net (code "150") (name "unconnected-(U$3-OB1-Pad11)") (class "Default")
      (node (ref "U$3") (pin "11") (pinfunction "OB1_11") (pintype "bidirectional"))
    )
    (net (code "151") (name "unconnected-(U$3-OB2-Pad13)") (class "Default")
      (node (ref "U$3") (pin "13") (pinfunction "OB2_13") (pintype "bidirectional"))
    )
    (net (code "152") (name "unconnected-(U$3-PDN{slash}UART-Pad20)") (class "Default")
      (node (ref "U$3") (pin "20") (pinfunction "PDN/UART_20") (pintype "bidirectional"))
    )
    (net (code "153") (name "unconnected-(U$3-SPREAD-Pad22)") (class "Default")
      (node (ref "U$3") (pin "22") (pinfunction "SPREAD_22") (pintype "bidirectional"))
    )
    (net (code "154") (name "unconnected-(U$3-STEP-Pad25)") (class "Default")
      (node (ref "U$3") (pin "25") (pinfunction "STEP_25") (pintype "bidirectional"))
    )
    (net (code "155") (name "unconnected-(U$3-VCC_IN-Pad16)") (class "Default")
      (node (ref "U$3") (pin "16") (pinfunction "VCC_IN_16") (pintype "bidirectional"))
    )
    (net (code "156") (name "unconnected-(U$3-VCC_IO-Pad19)") (class "Default")
      (node (ref "U$3") (pin "19") (pinfunction "VCC_IO_19") (pintype "bidirectional"))
    )
    (net (code "157") (name "unconnected-(U$3-VREF-Pad15)") (class "Default")
      (node (ref "U$3") (pin "15") (pinfunction "VREF_15") (pintype "bidirectional"))
    )
    (net (code "158") (name "unconnected-(X4-ID-Pad4)") (class "Default")
      (node (ref "X4") (pin "4") (pinfunction "ID_4") (pintype "bidirectional"))
    )
    (net (code "159") (name "~{RESET}") (class "Default")
      (node (ref "CH2") (pin "14") (pinfunction "RTS_14") (pintype "bidirectional"))
      (node (ref "IC3") (pin "90") (pinfunction "RESET_90") (pintype "input"))
      (node (ref "JP13") (pin "15") (pinfunction "15_15") (pintype "passive"))
      (node (ref "JP17") (pin "15") (pinfunction "15_15") (pintype "passive"))
    )
  )
)
